# ebox.net
KiCad netlist of a schematic drawn in EAGLE
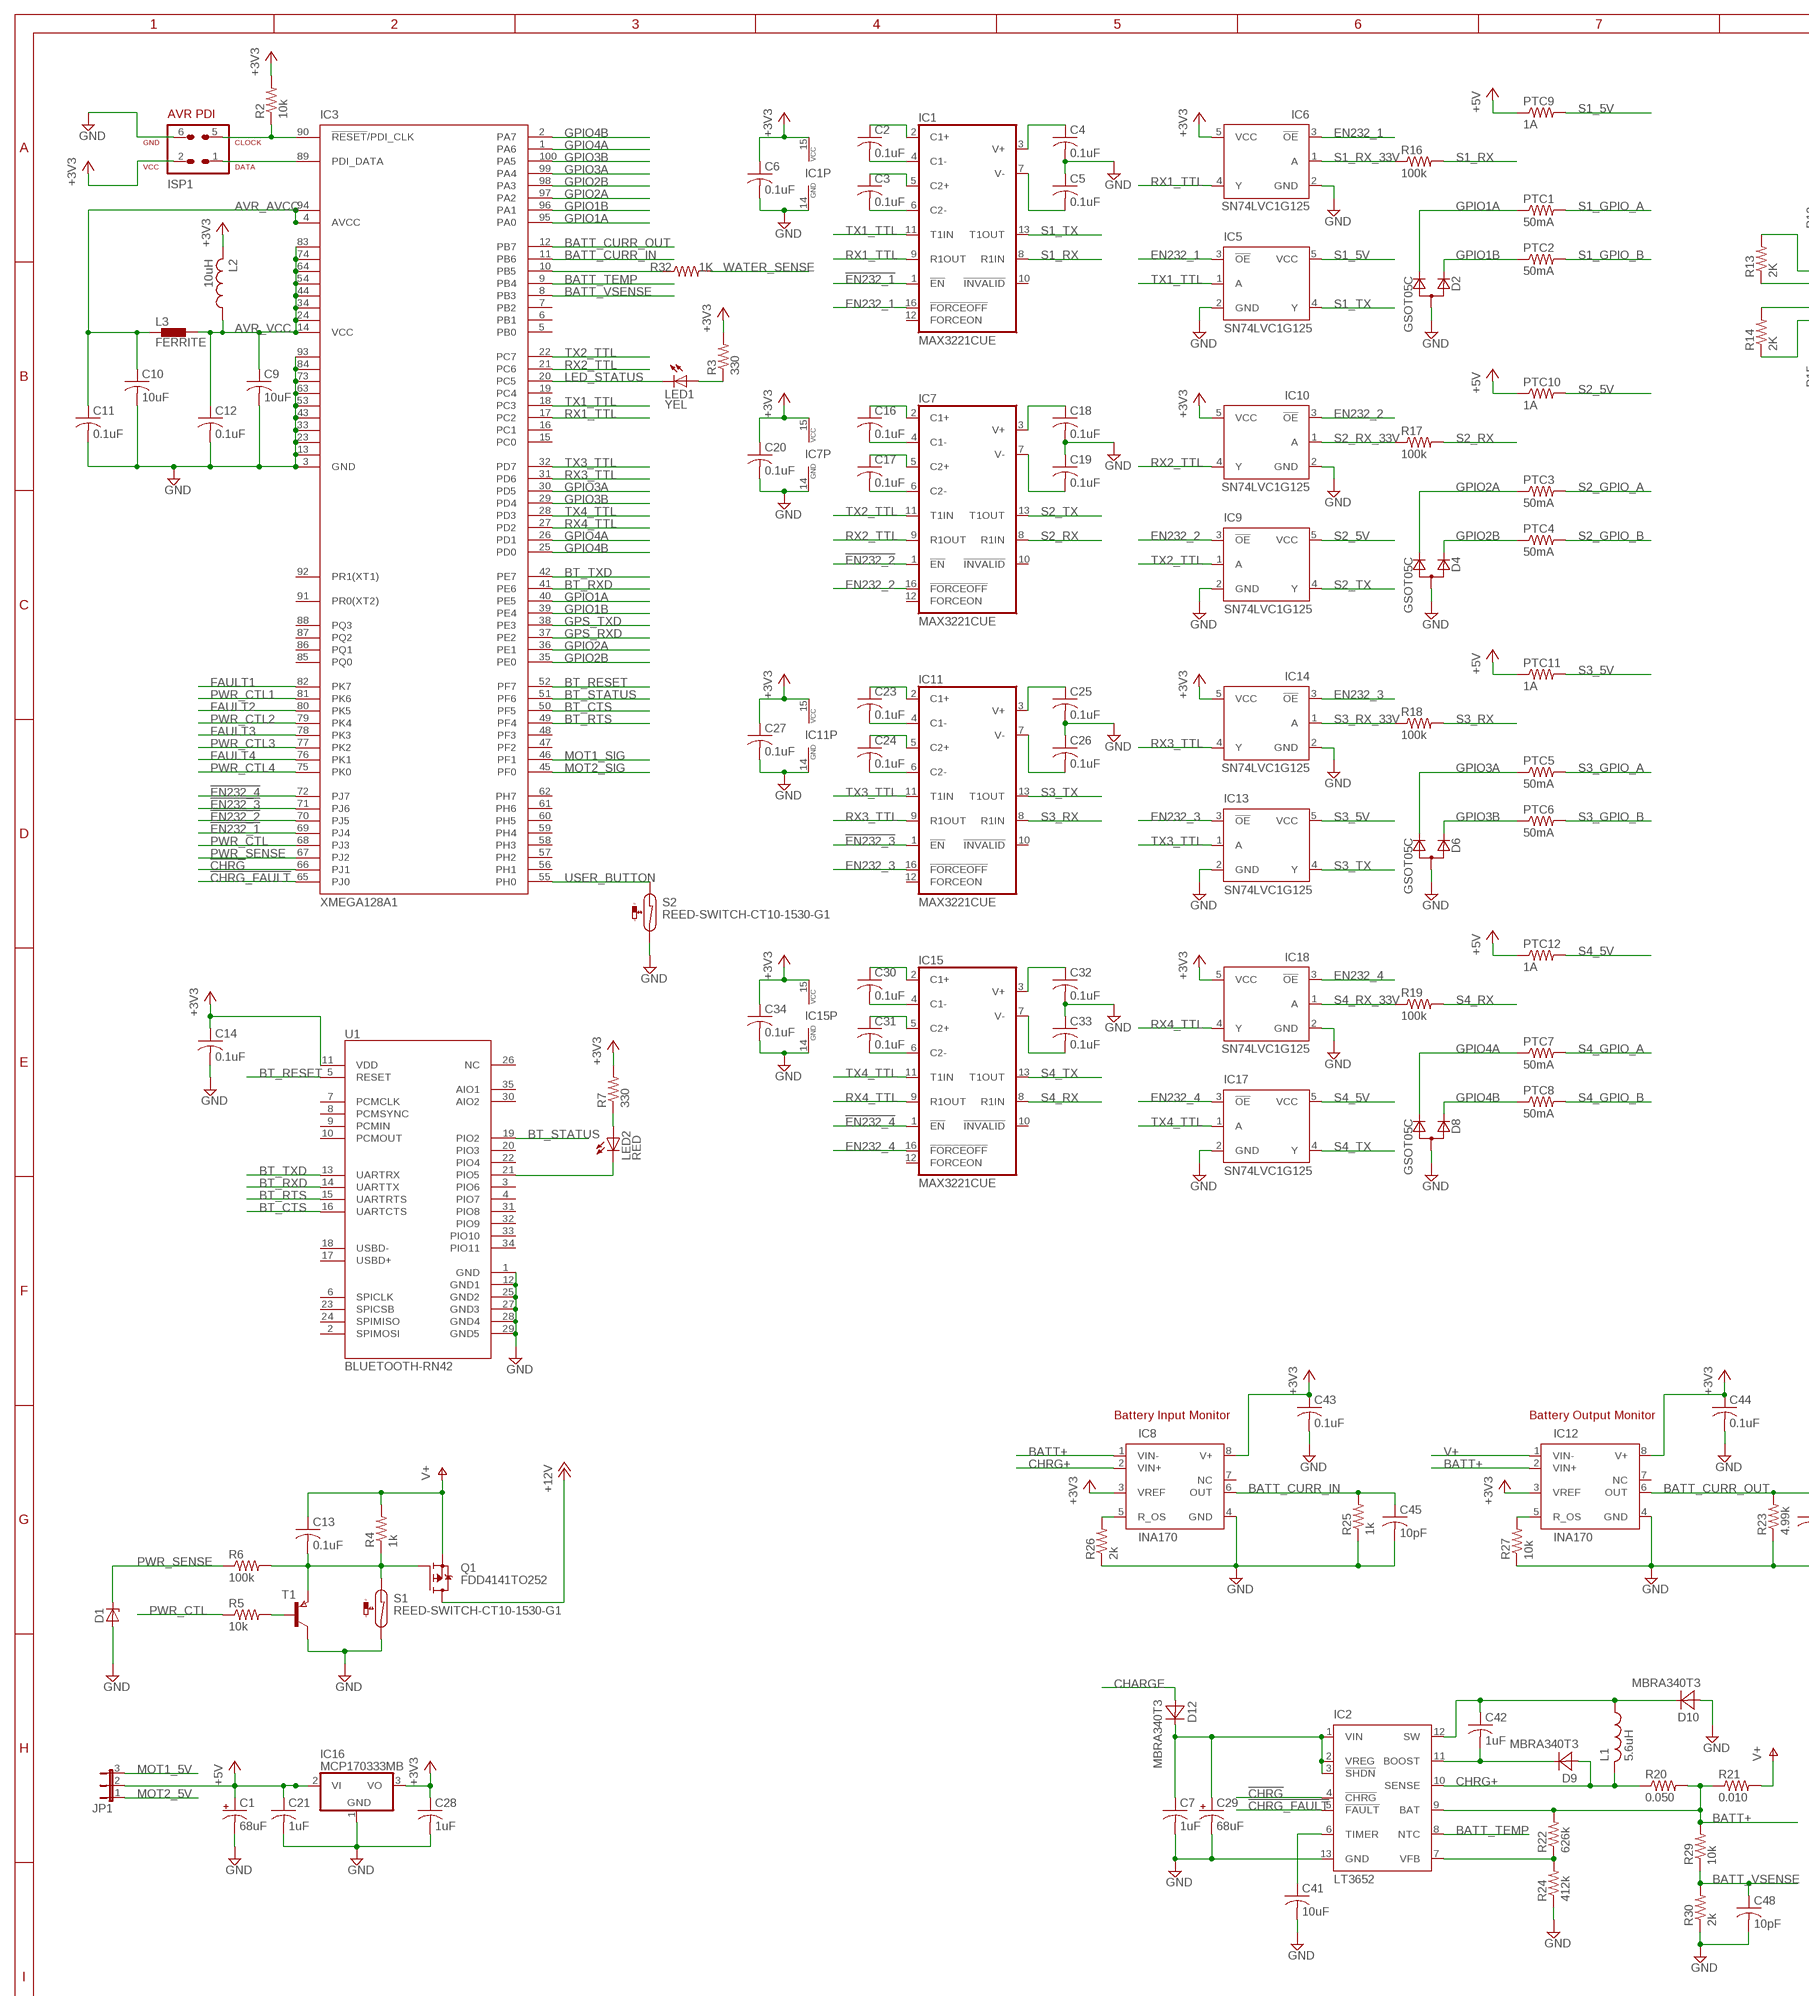
[diagram p0: schematic, sheet 1, part 1 of 2]
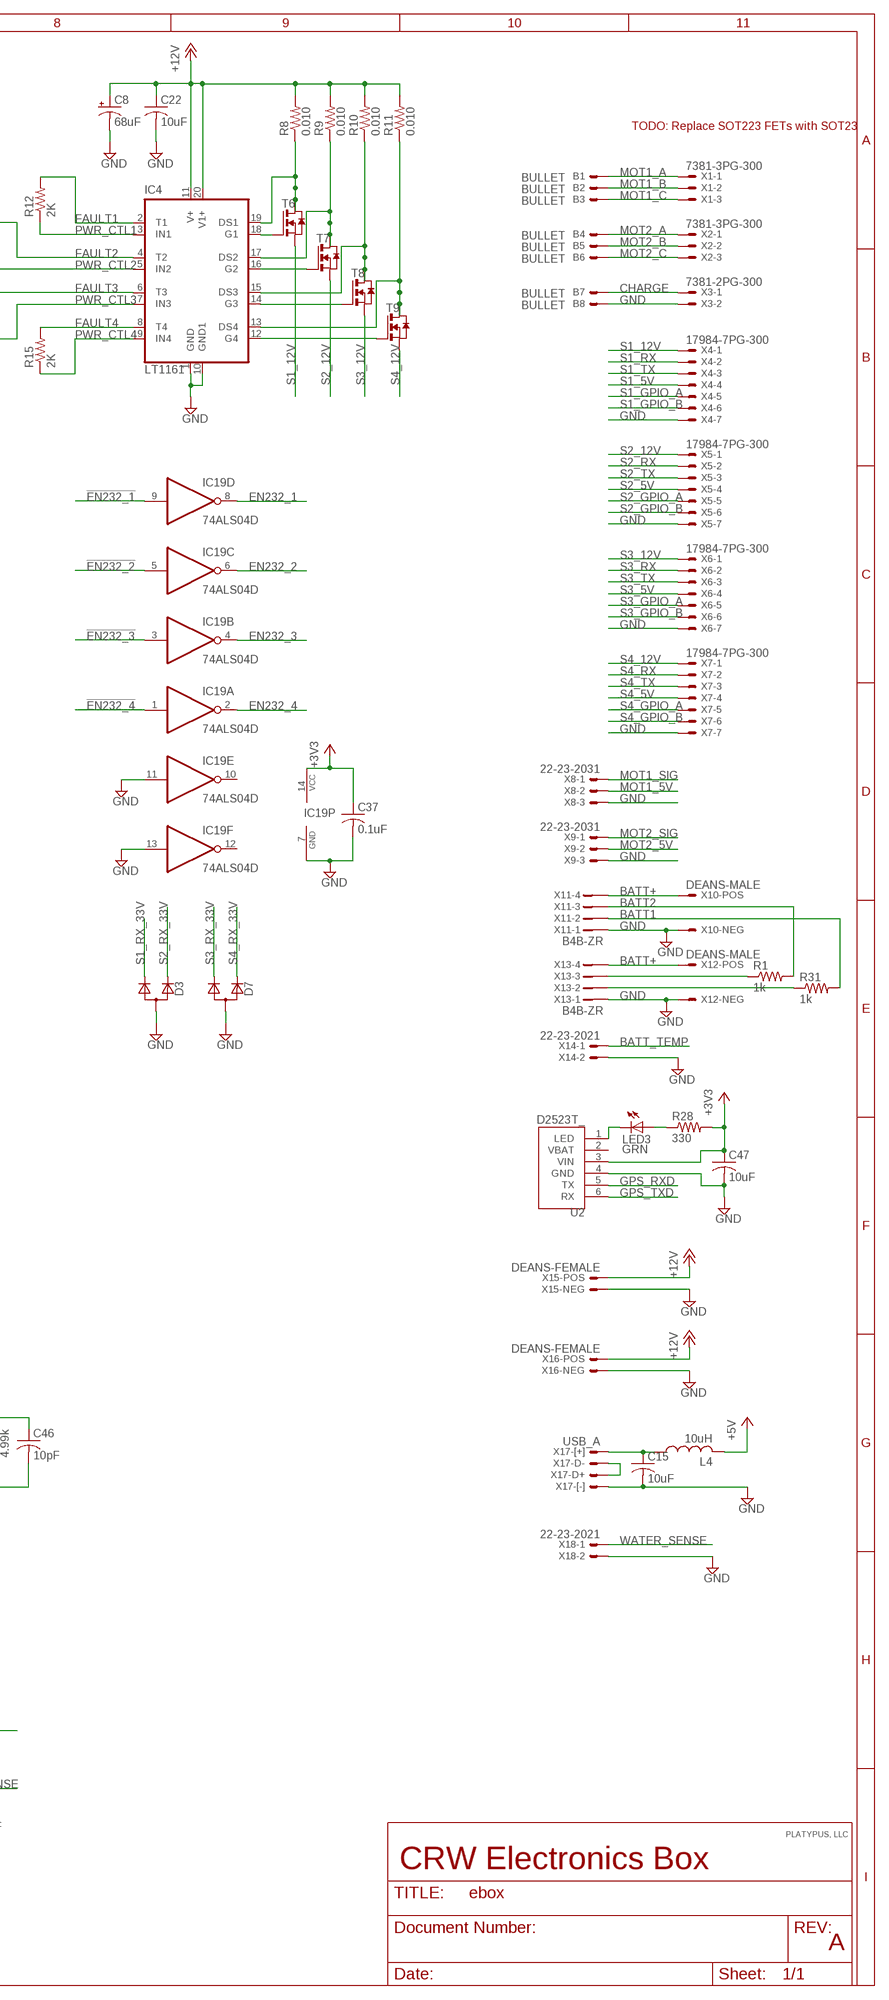
[diagram p1: schematic, sheet 1, part 2 of 2]

(export (version "E")
  (design (tool "Eeschema 10.0.6"))
  (components
    (comp (ref "B1")
      (value "BULLET")
      (footprint "eagle-import:BULLET")
      (libsource (lib "eagle-import") (part "BULLET"))
    )
    (comp (ref "B2")
      (value "BULLET")
      (footprint "eagle-import:BULLET")
      (libsource (lib "eagle-import") (part "BULLET"))
    )
    (comp (ref "B3")
      (value "BULLET")
      (footprint "eagle-import:BULLET")
      (libsource (lib "eagle-import") (part "BULLET"))
    )
    (comp (ref "B4")
      (value "BULLET")
      (footprint "eagle-import:BULLET")
      (libsource (lib "eagle-import") (part "BULLET"))
    )
    (comp (ref "B5")
      (value "BULLET")
      (footprint "eagle-import:BULLET")
      (libsource (lib "eagle-import") (part "BULLET"))
    )
    (comp (ref "B6")
      (value "BULLET")
      (footprint "eagle-import:BULLET")
      (libsource (lib "eagle-import") (part "BULLET"))
    )
    (comp (ref "B7")
      (value "BULLET")
      (footprint "eagle-import:BULLET")
      (libsource (lib "eagle-import") (part "BULLET"))
    )
    (comp (ref "B8")
      (value "BULLET")
      (footprint "eagle-import:BULLET")
      (libsource (lib "eagle-import") (part "BULLET"))
    )
    (comp (ref "C1")
      (value "68uF")
      (footprint "eagle-import:PANASONIC_D")
      (libsource (lib "eagle-import") (part "CPOL-USD"))
    )
    (comp (ref "C2")
      (value "0.1uF")
      (footprint "eagle-import:C0805")
      (libsource (lib "eagle-import") (part "C-USC0805"))
    )
    (comp (ref "C3")
      (value "0.1uF")
      (footprint "eagle-import:C0805")
      (libsource (lib "eagle-import") (part "C-USC0805"))
    )
    (comp (ref "C4")
      (value "0.1uF")
      (footprint "eagle-import:C0805")
      (libsource (lib "eagle-import") (part "C-USC0805"))
    )
    (comp (ref "C5")
      (value "0.1uF")
      (footprint "eagle-import:C0805")
      (libsource (lib "eagle-import") (part "C-USC0805"))
    )
    (comp (ref "C6")
      (value "0.1uF")
      (footprint "eagle-import:C0805")
      (libsource (lib "eagle-import") (part "C-USC0805"))
    )
    (comp (ref "C7")
      (value "1uF")
      (footprint "eagle-import:C0805")
      (libsource (lib "eagle-import") (part "C-USC0805"))
    )
    (comp (ref "C8")
      (value "68uF")
      (footprint "eagle-import:PANASONIC_D")
      (libsource (lib "eagle-import") (part "CPOL-USD"))
    )
    (comp (ref "C9")
      (value "10uF")
      (footprint "eagle-import:C0805")
      (libsource (lib "eagle-import") (part "C-USC0805"))
    )
    (comp (ref "C10")
      (value "10uF")
      (footprint "eagle-import:C0805")
      (libsource (lib "eagle-import") (part "C-USC0805"))
    )
    (comp (ref "C11")
      (value "0.1uF")
      (footprint "eagle-import:C0805")
      (libsource (lib "eagle-import") (part "C-USC0805"))
    )
    (comp (ref "C12")
      (value "0.1uF")
      (footprint "eagle-import:C0805")
      (libsource (lib "eagle-import") (part "C-USC0805"))
    )
    (comp (ref "C13")
      (value "0.1uF")
      (footprint "eagle-import:C0805")
      (libsource (lib "eagle-import") (part "C-USC0805"))
    )
    (comp (ref "C14")
      (value "0.1uF")
      (footprint "eagle-import:C0805")
      (libsource (lib "eagle-import") (part "C-USC0805"))
    )
    (comp (ref "C15")
      (value "10uF")
      (footprint "eagle-import:C0805")
      (libsource (lib "eagle-import") (part "C-USC0805"))
    )
    (comp (ref "C16")
      (value "0.1uF")
      (footprint "eagle-import:C0805")
      (libsource (lib "eagle-import") (part "C-USC0805"))
    )
    (comp (ref "C17")
      (value "0.1uF")
      (footprint "eagle-import:C0805")
      (libsource (lib "eagle-import") (part "C-USC0805"))
    )
    (comp (ref "C18")
      (value "0.1uF")
      (footprint "eagle-import:C0805")
      (libsource (lib "eagle-import") (part "C-USC0805"))
    )
    (comp (ref "C19")
      (value "0.1uF")
      (footprint "eagle-import:C0805")
      (libsource (lib "eagle-import") (part "C-USC0805"))
    )
    (comp (ref "C20")
      (value "0.1uF")
      (footprint "eagle-import:C0805")
      (libsource (lib "eagle-import") (part "C-USC0805"))
    )
    (comp (ref "C21")
      (value "1uF")
      (footprint "eagle-import:C0805")
      (libsource (lib "eagle-import") (part "C-USC0805"))
    )
    (comp (ref "C22")
      (value "10uF")
      (footprint "eagle-import:C0805")
      (libsource (lib "eagle-import") (part "C-USC0805"))
    )
    (comp (ref "C23")
      (value "0.1uF")
      (footprint "eagle-import:C0805")
      (libsource (lib "eagle-import") (part "C-USC0805"))
    )
    (comp (ref "C24")
      (value "0.1uF")
      (footprint "eagle-import:C0805")
      (libsource (lib "eagle-import") (part "C-USC0805"))
    )
    (comp (ref "C25")
      (value "0.1uF")
      (footprint "eagle-import:C0805")
      (libsource (lib "eagle-import") (part "C-USC0805"))
    )
    (comp (ref "C26")
      (value "0.1uF")
      (footprint "eagle-import:C0805")
      (libsource (lib "eagle-import") (part "C-USC0805"))
    )
    (comp (ref "C27")
      (value "0.1uF")
      (footprint "eagle-import:C0805")
      (libsource (lib "eagle-import") (part "C-USC0805"))
    )
    (comp (ref "C28")
      (value "1uF")
      (footprint "eagle-import:C0805")
      (libsource (lib "eagle-import") (part "C-USC0805"))
    )
    (comp (ref "C29")
      (value "68uF")
      (footprint "eagle-import:PANASONIC_D")
      (libsource (lib "eagle-import") (part "CPOL-USD"))
    )
    (comp (ref "C30")
      (value "0.1uF")
      (footprint "eagle-import:C0805")
      (libsource (lib "eagle-import") (part "C-USC0805"))
    )
    (comp (ref "C31")
      (value "0.1uF")
      (footprint "eagle-import:C0805")
      (libsource (lib "eagle-import") (part "C-USC0805"))
    )
    (comp (ref "C32")
      (value "0.1uF")
      (footprint "eagle-import:C0805")
      (libsource (lib "eagle-import") (part "C-USC0805"))
    )
    (comp (ref "C33")
      (value "0.1uF")
      (footprint "eagle-import:C0805")
      (libsource (lib "eagle-import") (part "C-USC0805"))
    )
    (comp (ref "C34")
      (value "0.1uF")
      (footprint "eagle-import:C0805")
      (libsource (lib "eagle-import") (part "C-USC0805"))
    )
    (comp (ref "C37")
      (value "0.1uF")
      (footprint "eagle-import:C0805")
      (libsource (lib "eagle-import") (part "C-USC0805"))
    )
    (comp (ref "C41")
      (value "10uF")
      (footprint "eagle-import:C0805")
      (libsource (lib "eagle-import") (part "C-USC0805"))
    )
    (comp (ref "C42")
      (value "1uF")
      (footprint "eagle-import:C0805")
      (libsource (lib "eagle-import") (part "C-USC0805"))
    )
    (comp (ref "C43")
      (value "0.1uF")
      (footprint "eagle-import:C0805")
      (libsource (lib "eagle-import") (part "C-USC0805"))
    )
    (comp (ref "C44")
      (value "0.1uF")
      (footprint "eagle-import:C0805")
      (libsource (lib "eagle-import") (part "C-USC0805"))
    )
    (comp (ref "C45")
      (value "10pF")
      (footprint "eagle-import:C0805")
      (libsource (lib "eagle-import") (part "C-USC0805"))
    )
    (comp (ref "C46")
      (value "10pF")
      (footprint "eagle-import:C0805")
      (libsource (lib "eagle-import") (part "C-USC0805"))
    )
    (comp (ref "C47")
      (value "10uF")
      (footprint "eagle-import:C0805")
      (libsource (lib "eagle-import") (part "C-USC0805"))
    )
    (comp (ref "C48")
      (value "10pF")
      (footprint "eagle-import:C0805")
      (libsource (lib "eagle-import") (part "C-USC0805"))
    )
    (comp (ref "D1")
      (value "ZENER-DIODESOT23")
      (footprint "eagle-import:SOT23")
      (libsource (lib "eagle-import") (part "ZENER-DIODESOT23"))
    )
    (comp (ref "D2")
      (value "GSOT05C")
      (footprint "eagle-import:SOT-23")
      (libsource (lib "eagle-import") (part "D_2CSOT23"))
    )
    (comp (ref "D3")
      (value "D_2CSOT23")
      (footprint "eagle-import:SOT-23")
      (libsource (lib "eagle-import") (part "D_2CSOT23"))
    )
    (comp (ref "D4")
      (value "GSOT05C")
      (footprint "eagle-import:SOT-23")
      (libsource (lib "eagle-import") (part "D_2CSOT23"))
    )
    (comp (ref "D6")
      (value "GSOT05C")
      (footprint "eagle-import:SOT-23")
      (libsource (lib "eagle-import") (part "D_2CSOT23"))
    )
    (comp (ref "D7")
      (value "D_2CSOT23")
      (footprint "eagle-import:SOT-23")
      (libsource (lib "eagle-import") (part "D_2CSOT23"))
    )
    (comp (ref "D8")
      (value "GSOT05C")
      (footprint "eagle-import:SOT-23")
      (libsource (lib "eagle-import") (part "D_2CSOT23"))
    )
    (comp (ref "D9")
      (value "MBRA340T3")
      (footprint "eagle-import:SMA")
      (libsource (lib "eagle-import") (part "MBRA340T3"))
    )
    (comp (ref "D10")
      (value "MBRA340T3")
      (footprint "eagle-import:SMA")
      (libsource (lib "eagle-import") (part "MBRA340T3"))
    )
    (comp (ref "D12")
      (value "MBRA340T3")
      (footprint "eagle-import:SMA")
      (libsource (lib "eagle-import") (part "MBRA340T3"))
    )
    (comp (ref "IC1")
      (value "MAX3221CUE")
      (footprint "eagle-import:TSSOP16")
      (fields (field (name "MF") "MAXIM") (field (name "MPN") "MAX3221CUE+"))
      (libsource (lib "eagle-import") (part "MAX3221UEC"))
    )
    (comp (ref "IC2")
      (value "LT3652")
      (footprint "eagle-import:MSOP12-MSE")
      (fields (field (name "MPN") "AD7992BRMZ-0"))
      (libsource (lib "eagle-import") (part "LT3652"))
    )
    (comp (ref "IC3")
      (value "XMEGA128A1")
      (footprint "eagle-import:TQFP100")
      (libsource (lib "eagle-import") (part "XMEGA128A1"))
    )
    (comp (ref "IC4")
      (value "LT1161")
      (footprint "eagle-import:SOIC20R")
      (libsource (lib "eagle-import") (part "LT1161"))
    )
    (comp (ref "IC5")
      (value "SN74LVC1G125")
      (footprint "eagle-import:SOT23-DBV")
      (libsource (lib "eagle-import") (part "SN74LVC1G125"))
    )
    (comp (ref "IC6")
      (value "SN74LVC1G125")
      (footprint "eagle-import:SOT23-DBV")
      (libsource (lib "eagle-import") (part "SN74LVC1G125"))
    )
    (comp (ref "IC7")
      (value "MAX3221CUE")
      (footprint "eagle-import:TSSOP16")
      (fields (field (name "MF") "MAXIM") (field (name "MPN") "MAX3221CUE+"))
      (libsource (lib "eagle-import") (part "MAX3221UEC"))
    )
    (comp (ref "IC8")
      (value "INA170")
      (footprint "eagle-import:MSOP8")
      (libsource (lib "eagle-import") (part "INA170"))
    )
    (comp (ref "IC9")
      (value "SN74LVC1G125")
      (footprint "eagle-import:SOT23-DBV")
      (libsource (lib "eagle-import") (part "SN74LVC1G125"))
    )
    (comp (ref "IC10")
      (value "SN74LVC1G125")
      (footprint "eagle-import:SOT23-DBV")
      (libsource (lib "eagle-import") (part "SN74LVC1G125"))
    )
    (comp (ref "IC11")
      (value "MAX3221CUE")
      (footprint "eagle-import:TSSOP16")
      (fields (field (name "MF") "MAXIM") (field (name "MPN") "MAX3221CUE+"))
      (libsource (lib "eagle-import") (part "MAX3221UEC"))
    )
    (comp (ref "IC12")
      (value "INA170")
      (footprint "eagle-import:MSOP8")
      (libsource (lib "eagle-import") (part "INA170"))
    )
    (comp (ref "IC13")
      (value "SN74LVC1G125")
      (footprint "eagle-import:SOT23-DBV")
      (libsource (lib "eagle-import") (part "SN74LVC1G125"))
    )
    (comp (ref "IC14")
      (value "SN74LVC1G125")
      (footprint "eagle-import:SOT23-DBV")
      (libsource (lib "eagle-import") (part "SN74LVC1G125"))
    )
    (comp (ref "IC15")
      (value "MAX3221CUE")
      (footprint "eagle-import:TSSOP16")
      (fields (field (name "MF") "MAXIM") (field (name "MPN") "MAX3221CUE+"))
      (libsource (lib "eagle-import") (part "MAX3221UEC"))
    )
    (comp (ref "IC16")
      (value "MCP170333MB")
      (footprint "eagle-import:SOT89")
      (libsource (lib "eagle-import") (part "MCP1703MB33"))
    )
    (comp (ref "IC17")
      (value "SN74LVC1G125")
      (footprint "eagle-import:SOT23-DBV")
      (libsource (lib "eagle-import") (part "SN74LVC1G125"))
    )
    (comp (ref "IC18")
      (value "SN74LVC1G125")
      (footprint "eagle-import:SOT23-DBV")
      (libsource (lib "eagle-import") (part "SN74LVC1G125"))
    )
    (comp (ref "IC19")
      (value "74ALS04D")
      (footprint "eagle-import:SO14")
      (libsource (lib "eagle-import") (part "7404DALS"))
    )
    (comp (ref "ISP1")
      (value "AVR-PDIVERT")
      (footprint "eagle-import:AVR-ISP-6")
      (libsource (lib "eagle-import") (part "AVR-PDIVERT"))
    )
    (comp (ref "JP1")
      (value "JP2E")
      (footprint "eagle-import:JP2")
      (libsource (lib "eagle-import") (part "JP2E"))
    )
    (comp (ref "L1")
      (value "5.6uH")
      (footprint "eagle-import:IHLP-2020CZ-11")
      (libsource (lib "eagle-import") (part "IHLP-2020CZ-11"))
    )
    (comp (ref "L2")
      (value "10uH")
      (footprint "eagle-import:L2012C")
      (libsource (lib "eagle-import") (part "L-USL2012C"))
    )
    (comp (ref "L3")
      (value "FERRITE")
      (footprint "eagle-import:0402")
      (libsource (lib "eagle-import") (part "BML15HB121SN1"))
    )
    (comp (ref "L4")
      (value "10uH")
      (footprint "eagle-import:L2012C")
      (libsource (lib "eagle-import") (part "L-USL2012C"))
    )
    (comp (ref "LED1")
      (value "YEL")
      (footprint "eagle-import:CHIPLED_1206")
      (libsource (lib "eagle-import") (part "LEDCHIPLED_1206"))
    )
    (comp (ref "LED2")
      (value "RED")
      (footprint "eagle-import:CHIPLED_1206")
      (libsource (lib "eagle-import") (part "LEDCHIPLED_1206"))
    )
    (comp (ref "LED3")
      (value "GRN")
      (footprint "eagle-import:CHIPLED_1206")
      (libsource (lib "eagle-import") (part "LEDCHIPLED_1206"))
    )
    (comp (ref "PTC1")
      (value "50mA")
      (footprint "eagle-import:R1206")
      (libsource (lib "eagle-import") (part "R-US_R1206"))
    )
    (comp (ref "PTC2")
      (value "50mA")
      (footprint "eagle-import:R1206")
      (libsource (lib "eagle-import") (part "R-US_R1206"))
    )
    (comp (ref "PTC3")
      (value "50mA")
      (footprint "eagle-import:R1206")
      (libsource (lib "eagle-import") (part "R-US_R1206"))
    )
    (comp (ref "PTC4")
      (value "50mA")
      (footprint "eagle-import:R1206")
      (libsource (lib "eagle-import") (part "R-US_R1206"))
    )
    (comp (ref "PTC5")
      (value "50mA")
      (footprint "eagle-import:R1206")
      (libsource (lib "eagle-import") (part "R-US_R1206"))
    )
    (comp (ref "PTC6")
      (value "50mA")
      (footprint "eagle-import:R1206")
      (libsource (lib "eagle-import") (part "R-US_R1206"))
    )
    (comp (ref "PTC7")
      (value "50mA")
      (footprint "eagle-import:R1206")
      (libsource (lib "eagle-import") (part "R-US_R1206"))
    )
    (comp (ref "PTC8")
      (value "50mA")
      (footprint "eagle-import:R1206")
      (libsource (lib "eagle-import") (part "R-US_R1206"))
    )
    (comp (ref "PTC9")
      (value "1A")
      (footprint "eagle-import:R1206")
      (libsource (lib "eagle-import") (part "R-US_R1206"))
    )
    (comp (ref "PTC10")
      (value "1A")
      (footprint "eagle-import:R1206")
      (libsource (lib "eagle-import") (part "R-US_R1206"))
    )
    (comp (ref "PTC11")
      (value "1A")
      (footprint "eagle-import:R1206")
      (libsource (lib "eagle-import") (part "R-US_R1206"))
    )
    (comp (ref "PTC12")
      (value "1A")
      (footprint "eagle-import:R1206")
      (libsource (lib "eagle-import") (part "R-US_R1206"))
    )
    (comp (ref "Q1")
      (value "FDD4141TO252")
      (footprint "eagle-import:TO252")
      (libsource (lib "eagle-import") (part "FDD4141TO252"))
    )
    (comp (ref "R1")
      (value "1k")
      (footprint "eagle-import:R0805")
      (libsource (lib "eagle-import") (part "R-US_R0805"))
    )
    (comp (ref "R2")
      (value "10k")
      (footprint "eagle-import:R0805")
      (libsource (lib "eagle-import") (part "R-US_R0805"))
    )
    (comp (ref "R3")
      (value "330")
      (footprint "eagle-import:R0805")
      (libsource (lib "eagle-import") (part "R-US_R0805"))
    )
    (comp (ref "R4")
      (value "1k")
      (footprint "eagle-import:R0805")
      (libsource (lib "eagle-import") (part "R-US_R0805"))
    )
    (comp (ref "R5")
      (value "10k")
      (footprint "eagle-import:R0805")
      (libsource (lib "eagle-import") (part "R-US_R0805"))
    )
    (comp (ref "R6")
      (value "100k")
      (footprint "eagle-import:R0805")
      (libsource (lib "eagle-import") (part "R-US_R0805"))
    )
    (comp (ref "R7")
      (value "330")
      (footprint "eagle-import:R0805")
      (libsource (lib "eagle-import") (part "R-US_R0805"))
    )
    (comp (ref "R8")
      (value "0.010")
      (footprint "eagle-import:R6332")
      (libsource (lib "eagle-import") (part "R-US_R6332"))
    )
    (comp (ref "R9")
      (value "0.010")
      (footprint "eagle-import:R6332")
      (libsource (lib "eagle-import") (part "R-US_R6332"))
    )
    (comp (ref "R10")
      (value "0.010")
      (footprint "eagle-import:R6332")
      (libsource (lib "eagle-import") (part "R-US_R6332"))
    )
    (comp (ref "R11")
      (value "0.010")
      (footprint "eagle-import:R6332")
      (libsource (lib "eagle-import") (part "R-US_R6332"))
    )
    (comp (ref "R12")
      (value "2K")
      (footprint "eagle-import:R0805")
      (libsource (lib "eagle-import") (part "R-US_R0805"))
    )
    (comp (ref "R13")
      (value "2K")
      (footprint "eagle-import:R0805")
      (libsource (lib "eagle-import") (part "R-US_R0805"))
    )
    (comp (ref "R14")
      (value "2K")
      (footprint "eagle-import:R0805")
      (libsource (lib "eagle-import") (part "R-US_R0805"))
    )
    (comp (ref "R15")
      (value "2K")
      (footprint "eagle-import:R0805")
      (libsource (lib "eagle-import") (part "R-US_R0805"))
    )
    (comp (ref "R16")
      (value "100k")
      (footprint "eagle-import:R0805")
      (libsource (lib "eagle-import") (part "R-US_R0805"))
    )
    (comp (ref "R17")
      (value "100k")
      (footprint "eagle-import:R0805")
      (libsource (lib "eagle-import") (part "R-US_R0805"))
    )
    (comp (ref "R18")
      (value "100k")
      (footprint "eagle-import:R0805")
      (libsource (lib "eagle-import") (part "R-US_R0805"))
    )
    (comp (ref "R19")
      (value "100k")
      (footprint "eagle-import:R0805")
      (libsource (lib "eagle-import") (part "R-US_R0805"))
    )
    (comp (ref "R20")
      (value "0.050")
      (footprint "eagle-import:R6332")
      (libsource (lib "eagle-import") (part "R-US_R6332"))
    )
    (comp (ref "R21")
      (value "0.010")
      (footprint "eagle-import:R6332")
      (libsource (lib "eagle-import") (part "R-US_R6332"))
    )
    (comp (ref "R22")
      (value "626k")
      (footprint "eagle-import:R0805")
      (libsource (lib "eagle-import") (part "R-US_R0805"))
    )
    (comp (ref "R23")
      (value "4.99k")
      (footprint "eagle-import:R0805")
      (libsource (lib "eagle-import") (part "R-US_R0805"))
    )
    (comp (ref "R24")
      (value "412k")
      (footprint "eagle-import:R0805")
      (libsource (lib "eagle-import") (part "R-US_R0805"))
    )
    (comp (ref "R25")
      (value "1k")
      (footprint "eagle-import:R0805")
      (libsource (lib "eagle-import") (part "R-US_R0805"))
    )
    (comp (ref "R26")
      (value "2k")
      (footprint "eagle-import:R0805")
      (libsource (lib "eagle-import") (part "R-US_R0805"))
    )
    (comp (ref "R27")
      (value "10k")
      (footprint "eagle-import:R0805")
      (libsource (lib "eagle-import") (part "R-US_R0805"))
    )
    (comp (ref "R28")
      (value "330")
      (footprint "eagle-import:R0805")
      (libsource (lib "eagle-import") (part "R-US_R0805"))
    )
    (comp (ref "R29")
      (value "10k")
      (footprint "eagle-import:R0805")
      (libsource (lib "eagle-import") (part "R-US_R0805"))
    )
    (comp (ref "R30")
      (value "2k")
      (footprint "eagle-import:R0805")
      (libsource (lib "eagle-import") (part "R-US_R0805"))
    )
    (comp (ref "R31")
      (value "1k")
      (footprint "eagle-import:R0805")
      (libsource (lib "eagle-import") (part "R-US_R0805"))
    )
    (comp (ref "R32")
      (value "1K")
      (footprint "eagle-import:R0805")
      (libsource (lib "eagle-import") (part "R-US_R0805"))
    )
    (comp (ref "S1")
      (value "REED-SWITCH-CT10-1530-G1")
      (footprint "eagle-import:CT10-G1")
      (fields (field (name "MF") "COTO TECHNOLOGY") (field (name "MPN") "CT10-1530-G1"))
      (libsource (lib "eagle-import") (part "REED-SWITCH-CT10-1530-G1"))
    )
    (comp (ref "S2")
      (value "REED-SWITCH-CT10-1530-G1")
      (footprint "eagle-import:CT10-G1")
      (fields (field (name "MF") "COTO TECHNOLOGY") (field (name "MPN") "CT10-1530-G1"))
      (libsource (lib "eagle-import") (part "REED-SWITCH-CT10-1530-G1"))
    )
    (comp (ref "T1")
      (value "PNPSOT23")
      (footprint "eagle-import:SOT-23")
      (fields (field (name "MPN") "DSS20200L-7"))
      (libsource (lib "eagle-import") (part "PNPSOT23"))
    )
    (comp (ref "T6")
      (value "NMOSSOT23-6")
      (footprint "eagle-import:SOT23-6")
      (libsource (lib "eagle-import") (part "NMOSSOT23-6"))
    )
    (comp (ref "T7")
      (value "NMOSSOT23-6")
      (footprint "eagle-import:SOT23-6")
      (libsource (lib "eagle-import") (part "NMOSSOT23-6"))
    )
    (comp (ref "T8")
      (value "NMOSSOT23-6")
      (footprint "eagle-import:SOT23-6")
      (libsource (lib "eagle-import") (part "NMOSSOT23-6"))
    )
    (comp (ref "T9")
      (value "NMOSSOT23-6")
      (footprint "eagle-import:SOT23-6")
      (libsource (lib "eagle-import") (part "NMOSSOT23-6"))
    )
    (comp (ref "U$1")
      (value "PLATYPUS_LOGO")
      (footprint "eagle-import:PLATYPUS_LOGO_SMALL")
      (libsource (lib "eagle-import") (part "PLATYPUS_LOGO"))
    )
    (comp (ref "U1")
      (value "BLUETOOTH-RN42")
      (footprint "eagle-import:RN41")
      (libsource (lib "eagle-import") (part "BLUETOOTH-RN41{dblquote}"))
    )
    (comp (ref "U2")
      (value "D2523T_")
      (footprint "eagle-import:EM406")
      (libsource (lib "eagle-import") (part "D2523T_"))
    )
    (comp (ref "X1")
      (value "7381-3PG-300")
      (footprint "eagle-import:7381-3PG-300")
      (libsource (lib "eagle-import") (part "7381-3PG-300"))
    )
    (comp (ref "X2")
      (value "7381-3PG-300")
      (footprint "eagle-import:7381-3PG-300")
      (libsource (lib "eagle-import") (part "7381-3PG-300"))
    )
    (comp (ref "X3")
      (value "7381-2PG-300")
      (footprint "eagle-import:7381-2PG-300")
      (libsource (lib "eagle-import") (part "7381-2PG-300"))
    )
    (comp (ref "X4")
      (value "17984-7PG-300")
      (footprint "eagle-import:17984-7PG-300")
      (libsource (lib "eagle-import") (part "17984-7PG-300"))
    )
    (comp (ref "X5")
      (value "17984-7PG-300")
      (footprint "eagle-import:17984-7PG-300")
      (libsource (lib "eagle-import") (part "17984-7PG-300"))
    )
    (comp (ref "X6")
      (value "17984-7PG-300")
      (footprint "eagle-import:17984-7PG-300")
      (libsource (lib "eagle-import") (part "17984-7PG-300"))
    )
    (comp (ref "X7")
      (value "17984-7PG-300")
      (footprint "eagle-import:17984-7PG-300")
      (libsource (lib "eagle-import") (part "17984-7PG-300"))
    )
    (comp (ref "X8")
      (value "22-23-2031")
      (footprint "eagle-import:22-23-2031")
      (fields (field (name "MF") "MOLEX"))
      (libsource (lib "eagle-import") (part "22-23-2031"))
    )
    (comp (ref "X9")
      (value "22-23-2031")
      (footprint "eagle-import:22-23-2031")
      (fields (field (name "MF") "MOLEX"))
      (libsource (lib "eagle-import") (part "22-23-2031"))
    )
    (comp (ref "X10")
      (value "DEANS-MALE")
      (footprint "eagle-import:DEANS_MALE")
      (libsource (lib "eagle-import") (part "DEANS-MALE"))
    )
    (comp (ref "X11")
      (value "B4B-ZR")
      (footprint "eagle-import:B4B-ZR")
      (fields (field (name "MF") "FARNELL") (field (name "MPN") "B4B-ZR(LF)(SN)"))
      (libsource (lib "eagle-import") (part "?4B-ZRB"))
    )
    (comp (ref "X12")
      (value "DEANS-MALE")
      (footprint "eagle-import:DEANS_MALE")
      (libsource (lib "eagle-import") (part "DEANS-MALE"))
    )
    (comp (ref "X13")
      (value "B4B-ZR")
      (footprint "eagle-import:B4B-ZR")
      (fields (field (name "MF") "FARNELL") (field (name "MPN") "B4B-ZR(LF)(SN)"))
      (libsource (lib "eagle-import") (part "?4B-ZRB"))
    )
    (comp (ref "X14")
      (value "22-23-2021")
      (footprint "eagle-import:22-23-2021")
      (fields (field (name "MF") "MOLEX"))
      (libsource (lib "eagle-import") (part "22-23-2021"))
    )
    (comp (ref "X15")
      (value "DEANS-FEMALE")
      (footprint "eagle-import:DEANS_FEMALE")
      (libsource (lib "eagle-import") (part "DEANS-FEMALE"))
    )
    (comp (ref "X16")
      (value "DEANS-FEMALE")
      (footprint "eagle-import:DEANS_FEMALE")
      (libsource (lib "eagle-import") (part "DEANS-FEMALE"))
    )
    (comp (ref "X17")
      (value "USB_A")
      (footprint "eagle-import:1001-002-01100")
      (libsource (lib "eagle-import") (part "USB_A"))
    )
    (comp (ref "X18")
      (value "22-23-2021")
      (footprint "eagle-import:22-23-2021")
      (fields
        (field (name "MF") "MOLEX")
        (field (name "MF_1") "MOLEX")
        (field (name "MPN") "22-23-2021")
        (field (name "OC_FARNELL") "1462926")
        (field (name "OC_NEWARK") "25C3832")
      )
      (libsource (lib "eagle-import") (part "22-23-2021"))
    )
  )
  (nets
    (net (code "1") (name "+3V3") (class "Default")
      (node (ref "C14") (pin "1") (pinfunction "1_1") (pintype "passive"))
      (node (ref "C20") (pin "1") (pinfunction "1_1") (pintype "passive"))
      (node (ref "C27") (pin "1") (pinfunction "1_1") (pintype "passive"))
      (node (ref "C28") (pin "1") (pinfunction "1_1") (pintype "passive"))
      (node (ref "C34") (pin "1") (pinfunction "1_1") (pintype "passive"))
      (node (ref "C37") (pin "1") (pinfunction "1_1") (pintype "passive"))
      (node (ref "C43") (pin "1") (pinfunction "1_1") (pintype "passive"))
      (node (ref "C44") (pin "1") (pinfunction "1_1") (pintype "passive"))
      (node (ref "C47") (pin "1") (pinfunction "1_1") (pintype "passive"))
      (node (ref "C6") (pin "1") (pinfunction "1_1") (pintype "passive"))
      (node (ref "IC1") (pin "15") (pinfunction "VCC_15") (pintype "power_in"))
      (node (ref "IC10") (pin "5") (pinfunction "VCC_5") (pintype "passive"))
      (node (ref "IC11") (pin "15") (pinfunction "VCC_15") (pintype "power_in"))
      (node (ref "IC12") (pin "3") (pinfunction "VREF_3") (pintype "input"))
      (node (ref "IC12") (pin "8") (pinfunction "V+_8") (pintype "input"))
      (node (ref "IC14") (pin "5") (pinfunction "VCC_5") (pintype "passive"))
      (node (ref "IC15") (pin "15") (pinfunction "VCC_15") (pintype "power_in"))
      (node (ref "IC16") (pin "3") (pinfunction "VO_3") (pintype "passive"))
      (node (ref "IC18") (pin "5") (pinfunction "VCC_5") (pintype "passive"))
      (node (ref "IC19") (pin "14") (pinfunction "VCC_14") (pintype "power_in"))
      (node (ref "IC6") (pin "5") (pinfunction "VCC_5") (pintype "passive"))
      (node (ref "IC7") (pin "15") (pinfunction "VCC_15") (pintype "power_in"))
      (node (ref "IC8") (pin "3") (pinfunction "VREF_3") (pintype "input"))
      (node (ref "IC8") (pin "8") (pinfunction "V+_8") (pintype "input"))
      (node (ref "ISP1") (pin "2") (pinfunction "2_2") (pintype "passive"))
      (node (ref "L2") (pin "2") (pinfunction "2_2") (pintype "passive"))
      (node (ref "R2") (pin "2") (pinfunction "2_2") (pintype "passive"))
      (node (ref "R28") (pin "2") (pinfunction "2_2") (pintype "passive"))
      (node (ref "R3") (pin "2") (pinfunction "2_2") (pintype "passive"))
      (node (ref "R7") (pin "2") (pinfunction "2_2") (pintype "passive"))
      (node (ref "U1") (pin "11") (pinfunction "VDD_11") (pintype "bidirectional"))
      (node (ref "U2") (pin "3") (pinfunction "VIN_3") (pintype "bidirectional"))
    )
    (net (code "2") (name "+5V") (class "Default")
      (node (ref "C1") (pin "+") (pinfunction "+_+") (pintype "passive"))
      (node (ref "C21") (pin "1") (pinfunction "1_1") (pintype "passive"))
      (node (ref "IC16") (pin "2") (pinfunction "VI_2") (pintype "input"))
      (node (ref "IC16") (pin "2@1") (pinfunction "VI1_2@1") (pintype "input"))
      (node (ref "JP1") (pin "2") (pinfunction "2_2") (pintype "passive"))
      (node (ref "L4") (pin "2") (pinfunction "2_2") (pintype "passive"))
      (node (ref "PTC10") (pin "1") (pinfunction "1_1") (pintype "passive"))
      (node (ref "PTC11") (pin "1") (pinfunction "1_1") (pintype "passive"))
      (node (ref "PTC12") (pin "1") (pinfunction "1_1") (pintype "passive"))
      (node (ref "PTC9") (pin "1") (pinfunction "1_1") (pintype "passive"))
    )
    (net (code "3") (name "+12V") (class "Default")
      (node (ref "C22") (pin "1") (pinfunction "1_1") (pintype "passive"))
      (node (ref "C8") (pin "+") (pinfunction "+_+") (pintype "passive"))
      (node (ref "IC4") (pin "11") (pinfunction "V+_11") (pintype "input"))
      (node (ref "IC4") (pin "20") (pinfunction "V1+_20") (pintype "input"))
      (node (ref "Q1") (pin "3") (pinfunction "D_3") (pintype "passive"))
      (node (ref "R10") (pin "2") (pinfunction "2_2") (pintype "passive"))
      (node (ref "R11") (pin "2") (pinfunction "2_2") (pintype "passive"))
      (node (ref "R8") (pin "2") (pinfunction "2_2") (pintype "passive"))
      (node (ref "R9") (pin "2") (pinfunction "2_2") (pintype "passive"))
      (node (ref "X15") (pin "POS") (pinfunction "S_POS") (pintype "passive"))
      (node (ref "X16") (pin "POS") (pinfunction "S_POS") (pintype "passive"))
    )
    (net (code "4") (name "/AVR_AVCC") (class "Default")
      (node (ref "C10") (pin "1") (pinfunction "1_1") (pintype "passive"))
      (node (ref "C11") (pin "1") (pinfunction "1_1") (pintype "passive"))
      (node (ref "IC3") (pin "4") (pinfunction "AVCC_4") (pintype "power_in"))
      (node (ref "IC3") (pin "94") (pinfunction "AVCC1_94") (pintype "power_in"))
      (node (ref "L3") (pin "1") (pinfunction "1_1") (pintype "passive"))
    )
    (net (code "5") (name "/AVR_VCC") (class "Default")
      (node (ref "C12") (pin "1") (pinfunction "1_1") (pintype "passive"))
      (node (ref "C9") (pin "1") (pinfunction "1_1") (pintype "passive"))
      (node (ref "IC3") (pin "14") (pinfunction "VCC_14") (pintype "power_in"))
      (node (ref "IC3") (pin "24") (pinfunction "VCC1_24") (pintype "power_in"))
      (node (ref "IC3") (pin "34") (pinfunction "VCC2_34") (pintype "power_in"))
      (node (ref "IC3") (pin "44") (pinfunction "VCC3_44") (pintype "power_in"))
      (node (ref "IC3") (pin "54") (pinfunction "VCC4_54") (pintype "power_in"))
      (node (ref "IC3") (pin "64") (pinfunction "VCC5_64") (pintype "power_in"))
      (node (ref "IC3") (pin "74") (pinfunction "VCC6_74") (pintype "power_in"))
      (node (ref "IC3") (pin "83") (pinfunction "VCC7_83") (pintype "power_in"))
      (node (ref "L2") (pin "1") (pinfunction "1_1") (pintype "passive"))
      (node (ref "L3") (pin "2") (pinfunction "2_2") (pintype "passive"))
    )
    (net (code "6") (name "/BATT+") (class "Default")
      (node (ref "IC12") (pin "2") (pinfunction "VIN+_2") (pintype "passive"))
      (node (ref "IC2") (pin "9") (pinfunction "BAT_9") (pintype "input"))
      (node (ref "IC8") (pin "1") (pinfunction "VIN-_1") (pintype "passive"))
      (node (ref "R20") (pin "2") (pinfunction "2_2") (pintype "passive"))
      (node (ref "R21") (pin "1") (pinfunction "1_1") (pintype "passive"))
      (node (ref "R22") (pin "2") (pinfunction "2_2") (pintype "passive"))
      (node (ref "R29") (pin "2") (pinfunction "2_2") (pintype "passive"))
      (node (ref "X10") (pin "POS") (pinfunction "S_POS") (pintype "passive"))
      (node (ref "X11") (pin "4") (pinfunction "1_4") (pintype "passive"))
      (node (ref "X12") (pin "POS") (pinfunction "S_POS") (pintype "passive"))
      (node (ref "X13") (pin "4") (pinfunction "1_4") (pintype "passive"))
    )
    (net (code "7") (name "/BATT1") (class "Default")
      (node (ref "R31") (pin "2") (pinfunction "2_2") (pintype "passive"))
      (node (ref "X11") (pin "2") (pinfunction "1_2") (pintype "passive"))
    )
    (net (code "8") (name "/BATT2") (class "Default")
      (node (ref "R1") (pin "2") (pinfunction "2_2") (pintype "passive"))
      (node (ref "X11") (pin "3") (pinfunction "1_3") (pintype "passive"))
    )
    (net (code "9") (name "/BATT_CURR_IN") (class "Default")
      (node (ref "C45") (pin "1") (pinfunction "1_1") (pintype "passive"))
      (node (ref "IC3") (pin "11") (pinfunction "PB6_11") (pintype "bidirectional"))
      (node (ref "IC8") (pin "6") (pinfunction "OUT_6") (pintype "passive"))
      (node (ref "R25") (pin "2") (pinfunction "2_2") (pintype "passive"))
    )
    (net (code "10") (name "/BATT_CURR_OUT") (class "Default")
      (node (ref "C46") (pin "1") (pinfunction "1_1") (pintype "passive"))
      (node (ref "IC12") (pin "6") (pinfunction "OUT_6") (pintype "passive"))
      (node (ref "IC3") (pin "12") (pinfunction "PB7_12") (pintype "bidirectional"))
      (node (ref "R23") (pin "2") (pinfunction "2_2") (pintype "passive"))
    )
    (net (code "11") (name "/BATT_TEMP") (class "Default")
      (node (ref "IC2") (pin "8") (pinfunction "NTC_8") (pintype "bidirectional"))
      (node (ref "IC3") (pin "9") (pinfunction "PB4_9") (pintype "bidirectional"))
      (node (ref "X14") (pin "1") (pinfunction "S_1") (pintype "passive"))
    )
    (net (code "12") (name "/BATT_VSENSE") (class "Default")
      (node (ref "C48") (pin "1") (pinfunction "1_1") (pintype "passive"))
      (node (ref "IC3") (pin "8") (pinfunction "PB3_8") (pintype "bidirectional"))
      (node (ref "R29") (pin "1") (pinfunction "1_1") (pintype "passive"))
      (node (ref "R30") (pin "2") (pinfunction "2_2") (pintype "passive"))
    )
    (net (code "13") (name "/BT_CTS") (class "Default")
      (node (ref "IC3") (pin "50") (pinfunction "PF5_50") (pintype "bidirectional"))
      (node (ref "U1") (pin "16") (pinfunction "UARTCTS_16") (pintype "bidirectional"))
    )
    (net (code "14") (name "/BT_RESET") (class "Default")
      (node (ref "IC3") (pin "52") (pinfunction "PF7_52") (pintype "bidirectional"))
      (node (ref "U1") (pin "5") (pinfunction "RESET_5") (pintype "bidirectional"))
    )
    (net (code "15") (name "/BT_RTS") (class "Default")
      (node (ref "IC3") (pin "49") (pinfunction "PF4_49") (pintype "bidirectional"))
      (node (ref "U1") (pin "15") (pinfunction "UARTRTS_15") (pintype "bidirectional"))
    )
    (net (code "16") (name "/BT_RXD") (class "Default")
      (node (ref "IC3") (pin "41") (pinfunction "PE6_41") (pintype "bidirectional"))
      (node (ref "U1") (pin "14") (pinfunction "UARTTX_14") (pintype "bidirectional"))
    )
    (net (code "17") (name "/BT_STATUS") (class "Default")
      (node (ref "IC3") (pin "51") (pinfunction "PF6_51") (pintype "bidirectional"))
      (node (ref "U1") (pin "19") (pinfunction "PIO2_19") (pintype "bidirectional"))
    )
    (net (code "18") (name "/BT_TXD") (class "Default")
      (node (ref "IC3") (pin "42") (pinfunction "PE7_42") (pintype "bidirectional"))
      (node (ref "U1") (pin "13") (pinfunction "UARTRX_13") (pintype "bidirectional"))
    )
    (net (code "19") (name "/CHARGE") (class "Default")
      (node (ref "B7") (pin "P$1") (pinfunction "S_P$1") (pintype "passive"))
      (node (ref "D12") (pin "A") (pinfunction "A_A") (pintype "passive"))
      (node (ref "X3") (pin "1") (pinfunction "S_1") (pintype "passive"))
    )
    (net (code "20") (name "/CHRG+") (class "Default")
      (node (ref "D9") (pin "A") (pinfunction "A_A") (pintype "passive"))
      (node (ref "IC2") (pin "10") (pinfunction "SENSE_10") (pintype "input"))
      (node (ref "IC8") (pin "2") (pinfunction "VIN+_2") (pintype "passive"))
      (node (ref "L1") (pin "2") (pinfunction "2_2") (pintype "passive"))
      (node (ref "R20") (pin "1") (pinfunction "1_1") (pintype "passive"))
    )
    (net (code "21") (name "/EN232_1") (class "Default")
      (node (ref "IC1") (pin "16") (pinfunction "~{FORCEOFF}_16") (pintype "input"))
      (node (ref "IC19") (pin "8") (pinfunction "O_8") (pintype "output"))
      (node (ref "IC5") (pin "3") (pinfunction "~{OE}_3") (pintype "input"))
      (node (ref "IC6") (pin "3") (pinfunction "~{OE}_3") (pintype "input"))
    )
    (net (code "22") (name "/EN232_2") (class "Default")
      (node (ref "IC10") (pin "3") (pinfunction "~{OE}_3") (pintype "input"))
      (node (ref "IC19") (pin "6") (pinfunction "O_6") (pintype "output"))
      (node (ref "IC7") (pin "16") (pinfunction "~{FORCEOFF}_16") (pintype "input"))
      (node (ref "IC9") (pin "3") (pinfunction "~{OE}_3") (pintype "input"))
    )
    (net (code "23") (name "/EN232_3") (class "Default")
      (node (ref "IC11") (pin "16") (pinfunction "~{FORCEOFF}_16") (pintype "input"))
      (node (ref "IC13") (pin "3") (pinfunction "~{OE}_3") (pintype "input"))
      (node (ref "IC14") (pin "3") (pinfunction "~{OE}_3") (pintype "input"))
      (node (ref "IC19") (pin "4") (pinfunction "O_4") (pintype "output"))
    )
    (net (code "24") (name "/EN232_4") (class "Default")
      (node (ref "IC15") (pin "16") (pinfunction "~{FORCEOFF}_16") (pintype "input"))
      (node (ref "IC17") (pin "3") (pinfunction "~{OE}_3") (pintype "input"))
      (node (ref "IC18") (pin "3") (pinfunction "~{OE}_3") (pintype "input"))
      (node (ref "IC19") (pin "2") (pinfunction "O_2") (pintype "output"))
    )
    (net (code "25") (name "/FAULT1") (class "Default")
      (node (ref "IC3") (pin "82") (pinfunction "PK7_82") (pintype "bidirectional"))
      (node (ref "IC4") (pin "2") (pinfunction "T1_2") (pintype "bidirectional"))
      (node (ref "R12") (pin "2") (pinfunction "2_2") (pintype "passive"))
    )
    (net (code "26") (name "/FAULT2") (class "Default")
      (node (ref "IC3") (pin "80") (pinfunction "PK5_80") (pintype "bidirectional"))
      (node (ref "IC4") (pin "4") (pinfunction "T2_4") (pintype "bidirectional"))
      (node (ref "R13") (pin "2") (pinfunction "2_2") (pintype "passive"))
    )
    (net (code "27") (name "/FAULT3") (class "Default")
      (node (ref "IC3") (pin "78") (pinfunction "PK3_78") (pintype "bidirectional"))
      (node (ref "IC4") (pin "6") (pinfunction "T3_6") (pintype "bidirectional"))
      (node (ref "R14") (pin "2") (pinfunction "2_2") (pintype "passive"))
    )
    (net (code "28") (name "/FAULT4") (class "Default")
      (node (ref "IC3") (pin "76") (pinfunction "PK1_76") (pintype "bidirectional"))
      (node (ref "IC4") (pin "8") (pinfunction "T4_8") (pintype "input"))
      (node (ref "R15") (pin "2") (pinfunction "2_2") (pintype "passive"))
    )
    (net (code "29") (name "/GPIO1A") (class "Default")
      (node (ref "D2") (pin "3") (pinfunction "C2_3") (pintype "passive"))
      (node (ref "IC3") (pin "40") (pinfunction "PE5_40") (pintype "bidirectional"))
      (node (ref "IC3") (pin "95") (pinfunction "PA0_95") (pintype "bidirectional"))
      (node (ref "PTC1") (pin "1") (pinfunction "1_1") (pintype "passive"))
    )
    (net (code "30") (name "/GPIO1B") (class "Default")
      (node (ref "D2") (pin "2") (pinfunction "C1_2") (pintype "passive"))
      (node (ref "IC3") (pin "39") (pinfunction "PE4_39") (pintype "bidirectional"))
      (node (ref "IC3") (pin "96") (pinfunction "PA1_96") (pintype "bidirectional"))
      (node (ref "PTC2") (pin "1") (pinfunction "1_1") (pintype "passive"))
    )
    (net (code "31") (name "/GPIO2A") (class "Default")
      (node (ref "D4") (pin "3") (pinfunction "C2_3") (pintype "passive"))
      (node (ref "IC3") (pin "36") (pinfunction "PE1_36") (pintype "bidirectional"))
      (node (ref "IC3") (pin "97") (pinfunction "PA2_97") (pintype "bidirectional"))
      (node (ref "PTC3") (pin "1") (pinfunction "1_1") (pintype "passive"))
    )
    (net (code "32") (name "/GPIO2B") (class "Default")
      (node (ref "D4") (pin "2") (pinfunction "C1_2") (pintype "passive"))
      (node (ref "IC3") (pin "35") (pinfunction "PE0_35") (pintype "bidirectional"))
      (node (ref "IC3") (pin "98") (pinfunction "PA3_98") (pintype "bidirectional"))
      (node (ref "PTC4") (pin "1") (pinfunction "1_1") (pintype "passive"))
    )
    (net (code "33") (name "/GPIO3A") (class "Default")
      (node (ref "D6") (pin "3") (pinfunction "C2_3") (pintype "passive"))
      (node (ref "IC3") (pin "30") (pinfunction "PD5_30") (pintype "bidirectional"))
      (node (ref "IC3") (pin "99") (pinfunction "PA4_99") (pintype "bidirectional"))
      (node (ref "PTC5") (pin "1") (pinfunction "1_1") (pintype "passive"))
    )
    (net (code "34") (name "/GPIO3B") (class "Default")
      (node (ref "D6") (pin "2") (pinfunction "C1_2") (pintype "passive"))
      (node (ref "IC3") (pin "100") (pinfunction "PA5_100") (pintype "bidirectional"))
      (node (ref "IC3") (pin "29") (pinfunction "PD4_29") (pintype "bidirectional"))
      (node (ref "PTC6") (pin "1") (pinfunction "1_1") (pintype "passive"))
    )
    (net (code "35") (name "/GPIO4A") (class "Default")
      (node (ref "D8") (pin "3") (pinfunction "C2_3") (pintype "passive"))
      (node (ref "IC3") (pin "1") (pinfunction "PA6_1") (pintype "bidirectional"))
      (node (ref "IC3") (pin "26") (pinfunction "PD1_26") (pintype "bidirectional"))
      (node (ref "PTC7") (pin "1") (pinfunction "1_1") (pintype "passive"))
    )
    (net (code "36") (name "/GPIO4B") (class "Default")
      (node (ref "D8") (pin "2") (pinfunction "C1_2") (pintype "passive"))
      (node (ref "IC3") (pin "2") (pinfunction "PA7_2") (pintype "bidirectional"))
      (node (ref "IC3") (pin "25") (pinfunction "PD0_25") (pintype "bidirectional"))
      (node (ref "PTC8") (pin "1") (pinfunction "1_1") (pintype "passive"))
    )
    (net (code "37") (name "/GPS_RXD") (class "Default")
      (node (ref "IC3") (pin "37") (pinfunction "PE2_37") (pintype "bidirectional"))
      (node (ref "U2") (pin "5") (pinfunction "TX_5") (pintype "bidirectional"))
    )
    (net (code "38") (name "/GPS_TXD") (class "Default")
      (node (ref "IC3") (pin "38") (pinfunction "PE3_38") (pintype "bidirectional"))
      (node (ref "U2") (pin "6") (pinfunction "RX_6") (pintype "bidirectional"))
    )
    (net (code "39") (name "/LED_STATUS") (class "Default")
      (node (ref "IC3") (pin "20") (pinfunction "PC5_20") (pintype "bidirectional"))
      (node (ref "LED1") (pin "C") (pinfunction "C_C") (pintype "passive"))
    )
    (net (code "40") (name "/MOT1_5V") (class "Default")
      (node (ref "JP1") (pin "3") (pinfunction "3_3") (pintype "passive"))
      (node (ref "X8") (pin "2") (pinfunction "S_2") (pintype "passive"))
    )
    (net (code "41") (name "/MOT1_A") (class "Default")
      (node (ref "B1") (pin "P$1") (pinfunction "S_P$1") (pintype "passive"))
      (node (ref "X1") (pin "1") (pinfunction "S_1") (pintype "passive"))
    )
    (net (code "42") (name "/MOT1_B") (class "Default")
      (node (ref "B2") (pin "P$1") (pinfunction "S_P$1") (pintype "passive"))
      (node (ref "X1") (pin "2") (pinfunction "S_2") (pintype "passive"))
    )
    (net (code "43") (name "/MOT1_C") (class "Default")
      (node (ref "B3") (pin "P$1") (pinfunction "S_P$1") (pintype "passive"))
      (node (ref "X1") (pin "3") (pinfunction "S_3") (pintype "passive"))
    )
    (net (code "44") (name "/MOT1_SIG") (class "Default")
      (node (ref "IC3") (pin "46") (pinfunction "PF1_46") (pintype "bidirectional"))
      (node (ref "X8") (pin "1") (pinfunction "S_1") (pintype "passive"))
    )
    (net (code "45") (name "/MOT2_5V") (class "Default")
      (node (ref "JP1") (pin "1") (pinfunction "1_1") (pintype "passive"))
      (node (ref "X9") (pin "2") (pinfunction "S_2") (pintype "passive"))
    )
    (net (code "46") (name "/MOT2_A") (class "Default")
      (node (ref "B4") (pin "P$1") (pinfunction "S_P$1") (pintype "passive"))
      (node (ref "X2") (pin "1") (pinfunction "S_1") (pintype "passive"))
    )
    (net (code "47") (name "/MOT2_B") (class "Default")
      (node (ref "B5") (pin "P$1") (pinfunction "S_P$1") (pintype "passive"))
      (node (ref "X2") (pin "2") (pinfunction "S_2") (pintype "passive"))
    )
    (net (code "48") (name "/MOT2_C") (class "Default")
      (node (ref "B6") (pin "P$1") (pinfunction "S_P$1") (pintype "passive"))
      (node (ref "X2") (pin "3") (pinfunction "S_3") (pintype "passive"))
    )
    (net (code "49") (name "/MOT2_SIG") (class "Default")
      (node (ref "IC3") (pin "45") (pinfunction "PF0_45") (pintype "bidirectional"))
      (node (ref "X9") (pin "1") (pinfunction "S_1") (pintype "passive"))
    )
    (net (code "50") (name "/PWR_CTL") (class "Default")
      (node (ref "IC3") (pin "68") (pinfunction "PJ3_68") (pintype "bidirectional"))
      (node (ref "R5") (pin "1") (pinfunction "1_1") (pintype "passive"))
    )
    (net (code "51") (name "/PWR_CTL1") (class "Default")
      (node (ref "IC3") (pin "81") (pinfunction "PK6_81") (pintype "bidirectional"))
      (node (ref "IC4") (pin "3") (pinfunction "IN1_3") (pintype "input"))
      (node (ref "R12") (pin "1") (pinfunction "1_1") (pintype "passive"))
    )
    (net (code "52") (name "/PWR_CTL2") (class "Default")
      (node (ref "IC3") (pin "79") (pinfunction "PK4_79") (pintype "bidirectional"))
      (node (ref "IC4") (pin "5") (pinfunction "IN2_5") (pintype "input"))
      (node (ref "R13") (pin "1") (pinfunction "1_1") (pintype "passive"))
    )
    (net (code "53") (name "/PWR_CTL3") (class "Default")
      (node (ref "IC3") (pin "77") (pinfunction "PK2_77") (pintype "bidirectional"))
      (node (ref "IC4") (pin "7") (pinfunction "IN3_7") (pintype "input"))
      (node (ref "R14") (pin "1") (pinfunction "1_1") (pintype "passive"))
    )
    (net (code "54") (name "/PWR_CTL4") (class "Default")
      (node (ref "IC3") (pin "75") (pinfunction "PK0_75") (pintype "bidirectional"))
      (node (ref "IC4") (pin "9") (pinfunction "IN4_9") (pintype "input"))
      (node (ref "R15") (pin "1") (pinfunction "1_1") (pintype "passive"))
    )
    (net (code "55") (name "/PWR_SENSE") (class "Default")
      (node (ref "D1") (pin "3") (pinfunction "C_3") (pintype "passive"))
      (node (ref "IC3") (pin "67") (pinfunction "PJ2_67") (pintype "bidirectional"))
      (node (ref "R6") (pin "1") (pinfunction "1_1") (pintype "passive"))
    )
    (net (code "56") (name "/RX1_TTL") (class "Default")
      (node (ref "IC1") (pin "9") (pinfunction "R1OUT_9") (pintype "output"))
      (node (ref "IC3") (pin "17") (pinfunction "PC2_17") (pintype "bidirectional"))
      (node (ref "IC6") (pin "4") (pinfunction "Y_4") (pintype "passive"))
    )
    (net (code "57") (name "/RX2_TTL") (class "Default")
      (node (ref "IC10") (pin "4") (pinfunction "Y_4") (pintype "passive"))
      (node (ref "IC3") (pin "21") (pinfunction "PC6_21") (pintype "bidirectional"))
      (node (ref "IC7") (pin "9") (pinfunction "R1OUT_9") (pintype "output"))
    )
    (net (code "58") (name "/RX3_TTL") (class "Default")
      (node (ref "IC11") (pin "9") (pinfunction "R1OUT_9") (pintype "output"))
      (node (ref "IC14") (pin "4") (pinfunction "Y_4") (pintype "passive"))
      (node (ref "IC3") (pin "31") (pinfunction "PD6_31") (pintype "bidirectional"))
    )
    (net (code "59") (name "/RX4_TTL") (class "Default")
      (node (ref "IC15") (pin "9") (pinfunction "R1OUT_9") (pintype "output"))
      (node (ref "IC18") (pin "4") (pinfunction "Y_4") (pintype "passive"))
      (node (ref "IC3") (pin "27") (pinfunction "PD2_27") (pintype "bidirectional"))
    )
    (net (code "60") (name "/S1_5V") (class "Default")
      (node (ref "IC5") (pin "5") (pinfunction "VCC_5") (pintype "passive"))
      (node (ref "PTC9") (pin "2") (pinfunction "2_2") (pintype "passive"))
      (node (ref "X4") (pin "4") (pinfunction "S_4") (pintype "passive"))
    )
    (net (code "61") (name "/S1_12V") (class "Default")
      (node (ref "T6") (pin "3") (pinfunction "S_3") (pintype "passive"))
      (node (ref "X4") (pin "1") (pinfunction "S_1") (pintype "passive"))
    )
    (net (code "62") (name "/S1_GPIO_A") (class "Default")
      (node (ref "PTC1") (pin "2") (pinfunction "2_2") (pintype "passive"))
      (node (ref "X4") (pin "5") (pinfunction "S_5") (pintype "passive"))
    )
    (net (code "63") (name "/S1_GPIO_B") (class "Default")
      (node (ref "PTC2") (pin "2") (pinfunction "2_2") (pintype "passive"))
      (node (ref "X4") (pin "6") (pinfunction "S_6") (pintype "passive"))
    )
    (net (code "64") (name "/S1_RX") (class "Default")
      (node (ref "IC1") (pin "8") (pinfunction "R1IN_8") (pintype "input"))
      (node (ref "R16") (pin "2") (pinfunction "2_2") (pintype "passive"))
      (node (ref "X4") (pin "2") (pinfunction "S_2") (pintype "passive"))
    )
    (net (code "65") (name "/S1_RX_33V") (class "Default")
      (node (ref "D3") (pin "3") (pinfunction "C2_3") (pintype "passive"))
      (node (ref "IC6") (pin "1") (pinfunction "A_1") (pintype "input"))
      (node (ref "R16") (pin "1") (pinfunction "1_1") (pintype "passive"))
    )
    (net (code "66") (name "/S1_TX") (class "Default")
      (node (ref "IC1") (pin "13") (pinfunction "T1OUT_13") (pintype "output"))
      (node (ref "IC5") (pin "4") (pinfunction "Y_4") (pintype "passive"))
      (node (ref "X4") (pin "3") (pinfunction "S_3") (pintype "passive"))
    )
    (net (code "67") (name "/S2_5V") (class "Default")
      (node (ref "IC9") (pin "5") (pinfunction "VCC_5") (pintype "passive"))
      (node (ref "PTC10") (pin "2") (pinfunction "2_2") (pintype "passive"))
      (node (ref "X5") (pin "4") (pinfunction "S_4") (pintype "passive"))
    )
    (net (code "68") (name "/S2_12V") (class "Default")
      (node (ref "T7") (pin "3") (pinfunction "S_3") (pintype "passive"))
      (node (ref "X5") (pin "1") (pinfunction "S_1") (pintype "passive"))
    )
    (net (code "69") (name "/S2_GPIO_A") (class "Default")
      (node (ref "PTC3") (pin "2") (pinfunction "2_2") (pintype "passive"))
      (node (ref "X5") (pin "5") (pinfunction "S_5") (pintype "passive"))
    )
    (net (code "70") (name "/S2_GPIO_B") (class "Default")
      (node (ref "PTC4") (pin "2") (pinfunction "2_2") (pintype "passive"))
      (node (ref "X5") (pin "6") (pinfunction "S_6") (pintype "passive"))
    )
    (net (code "71") (name "/S2_RX") (class "Default")
      (node (ref "IC7") (pin "8") (pinfunction "R1IN_8") (pintype "input"))
      (node (ref "R17") (pin "2") (pinfunction "2_2") (pintype "passive"))
      (node (ref "X5") (pin "2") (pinfunction "S_2") (pintype "passive"))
    )
    (net (code "72") (name "/S2_RX_33V") (class "Default")
      (node (ref "D3") (pin "2") (pinfunction "C1_2") (pintype "passive"))
      (node (ref "IC10") (pin "1") (pinfunction "A_1") (pintype "input"))
      (node (ref "R17") (pin "1") (pinfunction "1_1") (pintype "passive"))
    )
    (net (code "73") (name "/S2_TX") (class "Default")
      (node (ref "IC7") (pin "13") (pinfunction "T1OUT_13") (pintype "output"))
      (node (ref "IC9") (pin "4") (pinfunction "Y_4") (pintype "passive"))
      (node (ref "X5") (pin "3") (pinfunction "S_3") (pintype "passive"))
    )
    (net (code "74") (name "/S3_5V") (class "Default")
      (node (ref "IC13") (pin "5") (pinfunction "VCC_5") (pintype "passive"))
      (node (ref "PTC11") (pin "2") (pinfunction "2_2") (pintype "passive"))
      (node (ref "X6") (pin "4") (pinfunction "S_4") (pintype "passive"))
    )
    (net (code "75") (name "/S3_12V") (class "Default")
      (node (ref "T8") (pin "3") (pinfunction "S_3") (pintype "passive"))
      (node (ref "X6") (pin "1") (pinfunction "S_1") (pintype "passive"))
    )
    (net (code "76") (name "/S3_GPIO_A") (class "Default")
      (node (ref "PTC5") (pin "2") (pinfunction "2_2") (pintype "passive"))
      (node (ref "X6") (pin "5") (pinfunction "S_5") (pintype "passive"))
    )
    (net (code "77") (name "/S3_GPIO_B") (class "Default")
      (node (ref "PTC6") (pin "2") (pinfunction "2_2") (pintype "passive"))
      (node (ref "X6") (pin "6") (pinfunction "S_6") (pintype "passive"))
    )
    (net (code "78") (name "/S3_RX") (class "Default")
      (node (ref "IC11") (pin "8") (pinfunction "R1IN_8") (pintype "input"))
      (node (ref "R18") (pin "2") (pinfunction "2_2") (pintype "passive"))
      (node (ref "X6") (pin "2") (pinfunction "S_2") (pintype "passive"))
    )
    (net (code "79") (name "/S3_RX_33V") (class "Default")
      (node (ref "D7") (pin "3") (pinfunction "C2_3") (pintype "passive"))
      (node (ref "IC14") (pin "1") (pinfunction "A_1") (pintype "input"))
      (node (ref "R18") (pin "1") (pinfunction "1_1") (pintype "passive"))
    )
    (net (code "80") (name "/S3_TX") (class "Default")
      (node (ref "IC11") (pin "13") (pinfunction "T1OUT_13") (pintype "output"))
      (node (ref "IC13") (pin "4") (pinfunction "Y_4") (pintype "passive"))
      (node (ref "X6") (pin "3") (pinfunction "S_3") (pintype "passive"))
    )
    (net (code "81") (name "/S4_5V") (class "Default")
      (node (ref "IC17") (pin "5") (pinfunction "VCC_5") (pintype "passive"))
      (node (ref "PTC12") (pin "2") (pinfunction "2_2") (pintype "passive"))
      (node (ref "X7") (pin "4") (pinfunction "S_4") (pintype "passive"))
    )
    (net (code "82") (name "/S4_12V") (class "Default")
      (node (ref "T9") (pin "3") (pinfunction "S_3") (pintype "passive"))
      (node (ref "X7") (pin "1") (pinfunction "S_1") (pintype "passive"))
    )
    (net (code "83") (name "/S4_GPIO_A") (class "Default")
      (node (ref "PTC7") (pin "2") (pinfunction "2_2") (pintype "passive"))
      (node (ref "X7") (pin "5") (pinfunction "S_5") (pintype "passive"))
    )
    (net (code "84") (name "/S4_GPIO_B") (class "Default")
      (node (ref "PTC8") (pin "2") (pinfunction "2_2") (pintype "passive"))
      (node (ref "X7") (pin "6") (pinfunction "S_6") (pintype "passive"))
    )
    (net (code "85") (name "/S4_RX") (class "Default")
      (node (ref "IC15") (pin "8") (pinfunction "R1IN_8") (pintype "input"))
      (node (ref "R19") (pin "2") (pinfunction "2_2") (pintype "passive"))
      (node (ref "X7") (pin "2") (pinfunction "S_2") (pintype "passive"))
    )
    (net (code "86") (name "/S4_RX_33V") (class "Default")
      (node (ref "D7") (pin "2") (pinfunction "C1_2") (pintype "passive"))
      (node (ref "IC18") (pin "1") (pinfunction "A_1") (pintype "input"))
      (node (ref "R19") (pin "1") (pinfunction "1_1") (pintype "passive"))
    )
    (net (code "87") (name "/S4_TX") (class "Default")
      (node (ref "IC15") (pin "13") (pinfunction "T1OUT_13") (pintype "output"))
      (node (ref "IC17") (pin "4") (pinfunction "Y_4") (pintype "passive"))
      (node (ref "X7") (pin "3") (pinfunction "S_3") (pintype "passive"))
    )
    (net (code "88") (name "/TX1_TTL") (class "Default")
      (node (ref "IC1") (pin "11") (pinfunction "T1IN_11") (pintype "input"))
      (node (ref "IC3") (pin "18") (pinfunction "PC3_18") (pintype "bidirectional"))
      (node (ref "IC5") (pin "1") (pinfunction "A_1") (pintype "input"))
    )
    (net (code "89") (name "/TX2_TTL") (class "Default")
      (node (ref "IC3") (pin "22") (pinfunction "PC7_22") (pintype "bidirectional"))
      (node (ref "IC7") (pin "11") (pinfunction "T1IN_11") (pintype "input"))
      (node (ref "IC9") (pin "1") (pinfunction "A_1") (pintype "input"))
    )
    (net (code "90") (name "/TX3_TTL") (class "Default")
      (node (ref "IC11") (pin "11") (pinfunction "T1IN_11") (pintype "input"))
      (node (ref "IC13") (pin "1") (pinfunction "A_1") (pintype "input"))
      (node (ref "IC3") (pin "32") (pinfunction "PD7_32") (pintype "bidirectional"))
    )
    (net (code "91") (name "/TX4_TTL") (class "Default")
      (node (ref "IC15") (pin "11") (pinfunction "T1IN_11") (pintype "input"))
      (node (ref "IC17") (pin "1") (pinfunction "A_1") (pintype "input"))
      (node (ref "IC3") (pin "28") (pinfunction "PD3_28") (pintype "bidirectional"))
    )
    (net (code "92") (name "/USER_BUTTON") (class "Default")
      (node (ref "IC3") (pin "55") (pinfunction "PH0_55") (pintype "bidirectional"))
      (node (ref "S2") (pin "1") (pinfunction "1_1") (pintype "passive"))
    )
    (net (code "93") (name "/WATER_SENSE") (class "Default")
      (node (ref "R32") (pin "2") (pinfunction "2_2") (pintype "passive"))
      (node (ref "X18") (pin "1") (pinfunction "S_1") (pintype "passive"))
    )
    (net (code "94") (name "/~{CHRG_FAULT}") (class "Default")
      (node (ref "IC2") (pin "5") (pinfunction "~{FAULT}_5") (pintype "bidirectional"))
      (node (ref "IC3") (pin "65") (pinfunction "PJ0_65") (pintype "bidirectional"))
    )
    (net (code "95") (name "/~{CHRG}") (class "Default")
      (node (ref "IC2") (pin "4") (pinfunction "~{CHRG}_4") (pintype "bidirectional"))
      (node (ref "IC3") (pin "66") (pinfunction "PJ1_66") (pintype "bidirectional"))
    )
    (net (code "96") (name "/~{EN232_1}") (class "Default")
      (node (ref "IC1") (pin "1") (pinfunction "~{EN}_1") (pintype "input"))
      (node (ref "IC19") (pin "9") (pinfunction "I_9") (pintype "input"))
      (node (ref "IC3") (pin "69") (pinfunction "PJ4_69") (pintype "bidirectional"))
    )
    (net (code "97") (name "/~{EN232_2}") (class "Default")
      (node (ref "IC19") (pin "5") (pinfunction "I_5") (pintype "input"))
      (node (ref "IC3") (pin "70") (pinfunction "PJ5_70") (pintype "bidirectional"))
      (node (ref "IC7") (pin "1") (pinfunction "~{EN}_1") (pintype "input"))
    )
    (net (code "98") (name "/~{EN232_3}") (class "Default")
      (node (ref "IC11") (pin "1") (pinfunction "~{EN}_1") (pintype "input"))
      (node (ref "IC19") (pin "3") (pinfunction "I_3") (pintype "input"))
      (node (ref "IC3") (pin "71") (pinfunction "PJ6_71") (pintype "bidirectional"))
    )
    (net (code "99") (name "/~{EN232_4}") (class "Default")
      (node (ref "IC15") (pin "1") (pinfunction "~{EN}_1") (pintype "input"))
      (node (ref "IC19") (pin "1") (pinfunction "I_1") (pintype "input"))
      (node (ref "IC3") (pin "72") (pinfunction "PJ7_72") (pintype "bidirectional"))
    )
    (net (code "100") (name "GND") (class "Default")
      (node (ref "B8") (pin "P$1") (pinfunction "S_P$1") (pintype "passive"))
      (node (ref "C1") (pin "-") (pinfunction "-_-") (pintype "passive"))
      (node (ref "C10") (pin "2") (pinfunction "2_2") (pintype "passive"))
      (node (ref "C11") (pin "2") (pinfunction "2_2") (pintype "passive"))
      (node (ref "C12") (pin "2") (pinfunction "2_2") (pintype "passive"))
      (node (ref "C14") (pin "2") (pinfunction "2_2") (pintype "passive"))
      (node (ref "C15") (pin "2") (pinfunction "2_2") (pintype "passive"))
      (node (ref "C18") (pin "2") (pinfunction "2_2") (pintype "passive"))
      (node (ref "C19") (pin "1") (pinfunction "1_1") (pintype "passive"))
      (node (ref "C20") (pin "2") (pinfunction "2_2") (pintype "passive"))
      (node (ref "C21") (pin "2") (pinfunction "2_2") (pintype "passive"))
      (node (ref "C22") (pin "2") (pinfunction "2_2") (pintype "passive"))
      (node (ref "C25") (pin "2") (pinfunction "2_2") (pintype "passive"))
      (node (ref "C26") (pin "1") (pinfunction "1_1") (pintype "passive"))
      (node (ref "C27") (pin "2") (pinfunction "2_2") (pintype "passive"))
      (node (ref "C28") (pin "2") (pinfunction "2_2") (pintype "passive"))
      (node (ref "C29") (pin "-") (pinfunction "-_-") (pintype "passive"))
      (node (ref "C32") (pin "2") (pinfunction "2_2") (pintype "passive"))
      (node (ref "C33") (pin "1") (pinfunction "1_1") (pintype "passive"))
      (node (ref "C34") (pin "2") (pinfunction "2_2") (pintype "passive"))
      (node (ref "C37") (pin "2") (pinfunction "2_2") (pintype "passive"))
      (node (ref "C4") (pin "2") (pinfunction "2_2") (pintype "passive"))
      (node (ref "C41") (pin "2") (pinfunction "2_2") (pintype "passive"))
      (node (ref "C43") (pin "2") (pinfunction "2_2") (pintype "passive"))
      (node (ref "C44") (pin "2") (pinfunction "2_2") (pintype "passive"))
      (node (ref "C45") (pin "2") (pinfunction "2_2") (pintype "passive"))
      (node (ref "C46") (pin "2") (pinfunction "2_2") (pintype "passive"))
      (node (ref "C47") (pin "2") (pinfunction "2_2") (pintype "passive"))
      (node (ref "C48") (pin "2") (pinfunction "2_2") (pintype "passive"))
      (node (ref "C5") (pin "1") (pinfunction "1_1") (pintype "passive"))
      (node (ref "C6") (pin "2") (pinfunction "2_2") (pintype "passive"))
      (node (ref "C7") (pin "2") (pinfunction "2_2") (pintype "passive"))
      (node (ref "C8") (pin "-") (pinfunction "-_-") (pintype "passive"))
      (node (ref "C9") (pin "2") (pinfunction "2_2") (pintype "passive"))
      (node (ref "D1") (pin "1") (pinfunction "A_1") (pintype "passive"))
      (node (ref "D10") (pin "A") (pinfunction "A_A") (pintype "passive"))
      (node (ref "D2") (pin "1") (pinfunction "A_1") (pintype "passive"))
      (node (ref "D3") (pin "1") (pinfunction "A_1") (pintype "passive"))
      (node (ref "D4") (pin "1") (pinfunction "A_1") (pintype "passive"))
      (node (ref "D6") (pin "1") (pinfunction "A_1") (pintype "passive"))
      (node (ref "D7") (pin "1") (pinfunction "A_1") (pintype "passive"))
      (node (ref "D8") (pin "1") (pinfunction "A_1") (pintype "passive"))
      (node (ref "IC1") (pin "14") (pinfunction "GND_14") (pintype "power_in"))
      (node (ref "IC10") (pin "2") (pinfunction "GND_2") (pintype "power_in"))
      (node (ref "IC11") (pin "14") (pinfunction "GND_14") (pintype "power_in"))
      (node (ref "IC12") (pin "4") (pinfunction "GND_4") (pintype "power_in"))
      (node (ref "IC13") (pin "2") (pinfunction "GND_2") (pintype "power_in"))
      (node (ref "IC14") (pin "2") (pinfunction "GND_2") (pintype "power_in"))
      (node (ref "IC15") (pin "14") (pinfunction "GND_14") (pintype "power_in"))
      (node (ref "IC16") (pin "1") (pinfunction "GND_1") (pintype "passive"))
      (node (ref "IC17") (pin "2") (pinfunction "GND_2") (pintype "power_in"))
      (node (ref "IC18") (pin "2") (pinfunction "GND_2") (pintype "power_in"))
      (node (ref "IC19") (pin "11") (pinfunction "I_11") (pintype "input"))
      (node (ref "IC19") (pin "13") (pinfunction "I_13") (pintype "input"))
      (node (ref "IC19") (pin "7") (pinfunction "GND_7") (pintype "power_in"))
      (node (ref "IC2") (pin "13") (pinfunction "GND_13") (pintype "power_in"))
      (node (ref "IC3") (pin "13") (pinfunction "GND1_13") (pintype "power_in"))
      (node (ref "IC3") (pin "23") (pinfunction "GND2_23") (pintype "power_in"))
      (node (ref "IC3") (pin "3") (pinfunction "GND_3") (pintype "power_in"))
      (node (ref "IC3") (pin "33") (pinfunction "GND3_33") (pintype "power_in"))
      (node (ref "IC3") (pin "43") (pinfunction "GND4_43") (pintype "power_in"))
      (node (ref "IC3") (pin "53") (pinfunction "GND5_53") (pintype "power_in"))
      (node (ref "IC3") (pin "63") (pinfunction "GND6_63") (pintype "power_in"))
      (node (ref "IC3") (pin "73") (pinfunction "GND7_73") (pintype "power_in"))
      (node (ref "IC3") (pin "84") (pinfunction "GND8_84") (pintype "power_in"))
      (node (ref "IC3") (pin "93") (pinfunction "GND9_93") (pintype "power_in"))
      (node (ref "IC4") (pin "1") (pinfunction "GND_1") (pintype "input"))
      (node (ref "IC4") (pin "10") (pinfunction "GND1_10") (pintype "input"))
      (node (ref "IC5") (pin "2") (pinfunction "GND_2") (pintype "power_in"))
      (node (ref "IC6") (pin "2") (pinfunction "GND_2") (pintype "power_in"))
      (node (ref "IC7") (pin "14") (pinfunction "GND_14") (pintype "power_in"))
      (node (ref "IC8") (pin "4") (pinfunction "GND_4") (pintype "power_in"))
      (node (ref "IC9") (pin "2") (pinfunction "GND_2") (pintype "power_in"))
      (node (ref "ISP1") (pin "6") (pinfunction "6_6") (pintype "passive"))
      (node (ref "R23") (pin "1") (pinfunction "1_1") (pintype "passive"))
      (node (ref "R24") (pin "1") (pinfunction "1_1") (pintype "passive"))
      (node (ref "R25") (pin "1") (pinfunction "1_1") (pintype "passive"))
      (node (ref "R26") (pin "1") (pinfunction "1_1") (pintype "passive"))
      (node (ref "R27") (pin "1") (pinfunction "1_1") (pintype "passive"))
      (node (ref "R30") (pin "1") (pinfunction "1_1") (pintype "passive"))
      (node (ref "S1") (pin "2") (pinfunction "2_2") (pintype "passive"))
      (node (ref "S2") (pin "2") (pinfunction "2_2") (pintype "passive"))
      (node (ref "T1") (pin "1") (pinfunction "C_1") (pintype "passive"))
      (node (ref "U1") (pin "1") (pinfunction "GND_1") (pintype "bidirectional"))
      (node (ref "U1") (pin "12") (pinfunction "GND1_12") (pintype "bidirectional"))
      (node (ref "U1") (pin "25") (pinfunction "GND2_25") (pintype "bidirectional"))
      (node (ref "U1") (pin "27") (pinfunction "GND3_27") (pintype "bidirectional"))
      (node (ref "U1") (pin "28") (pinfunction "GND4_28") (pintype "bidirectional"))
      (node (ref "U1") (pin "29") (pinfunction "GND5_29") (pintype "bidirectional"))
      (node (ref "U2") (pin "4") (pinfunction "GND_4") (pintype "bidirectional"))
      (node (ref "X10") (pin "NEG") (pinfunction "S_NEG") (pintype "passive"))
      (node (ref "X11") (pin "1") (pinfunction "1_1") (pintype "passive"))
      (node (ref "X12") (pin "NEG") (pinfunction "S_NEG") (pintype "passive"))
      (node (ref "X13") (pin "1") (pinfunction "1_1") (pintype "passive"))
      (node (ref "X14") (pin "2") (pinfunction "S_2") (pintype "passive"))
      (node (ref "X15") (pin "NEG") (pinfunction "S_NEG") (pintype "passive"))
      (node (ref "X16") (pin "NEG") (pinfunction "S_NEG") (pintype "passive"))
      (node (ref "X17") (pin "4") (pinfunction "S_4") (pintype "passive"))
      (node (ref "X18") (pin "2") (pinfunction "S_2") (pintype "passive"))
      (node (ref "X3") (pin "2") (pinfunction "S_2") (pintype "passive"))
      (node (ref "X4") (pin "7") (pinfunction "S_7") (pintype "passive"))
      (node (ref "X5") (pin "7") (pinfunction "S_7") (pintype "passive"))
      (node (ref "X6") (pin "7") (pinfunction "S_7") (pintype "passive"))
      (node (ref "X7") (pin "7") (pinfunction "S_7") (pintype "passive"))
      (node (ref "X8") (pin "3") (pinfunction "S_3") (pintype "passive"))
      (node (ref "X9") (pin "3") (pinfunction "S_3") (pintype "passive"))
    )
    (net (code "101") (name "Net-(IC1A-C1+)") (class "Default")
      (node (ref "C2") (pin "1") (pinfunction "1_1") (pintype "passive"))
      (node (ref "IC1") (pin "2") (pinfunction "C1+_2") (pintype "passive"))
    )
    (net (code "102") (name "Net-(IC1A-C1-)") (class "Default")
      (node (ref "C2") (pin "2") (pinfunction "2_2") (pintype "passive"))
      (node (ref "IC1") (pin "4") (pinfunction "C1-_4") (pintype "passive"))
    )
    (net (code "103") (name "Net-(IC1A-C2+)") (class "Default")
      (node (ref "C3") (pin "1") (pinfunction "1_1") (pintype "passive"))
      (node (ref "IC1") (pin "5") (pinfunction "C2+_5") (pintype "passive"))
    )
    (net (code "104") (name "Net-(IC1A-C2-)") (class "Default")
      (node (ref "C3") (pin "2") (pinfunction "2_2") (pintype "passive"))
      (node (ref "IC1") (pin "6") (pinfunction "C2-_6") (pintype "passive"))
    )
    (net (code "105") (name "Net-(IC1A-V+)") (class "Default")
      (node (ref "C4") (pin "1") (pinfunction "1_1") (pintype "passive"))
      (node (ref "IC1") (pin "3") (pinfunction "V+_3") (pintype "passive"))
    )
    (net (code "106") (name "Net-(IC1A-V-)") (class "Default")
      (node (ref "C5") (pin "2") (pinfunction "2_2") (pintype "passive"))
      (node (ref "IC1") (pin "7") (pinfunction "V-_7") (pintype "passive"))
    )
    (net (code "107") (name "Net-(IC2-BOOST)") (class "Default")
      (node (ref "C42") (pin "2") (pinfunction "2_2") (pintype "passive"))
      (node (ref "D9") (pin "C") (pinfunction "C_C") (pintype "passive"))
      (node (ref "IC2") (pin "11") (pinfunction "BOOST_11") (pintype "output"))
    )
    (net (code "108") (name "Net-(IC2-SW)") (class "Default")
      (node (ref "C42") (pin "1") (pinfunction "1_1") (pintype "passive"))
      (node (ref "D10") (pin "C") (pinfunction "C_C") (pintype "passive"))
      (node (ref "IC2") (pin "12") (pinfunction "SW_12") (pintype "input"))
      (node (ref "L1") (pin "1") (pinfunction "1_1") (pintype "passive"))
    )
    (net (code "109") (name "Net-(IC2-TIMER)") (class "Default")
      (node (ref "C41") (pin "1") (pinfunction "1_1") (pintype "passive"))
      (node (ref "IC2") (pin "6") (pinfunction "TIMER_6") (pintype "bidirectional"))
    )
    (net (code "110") (name "Net-(IC2-VFB)") (class "Default")
      (node (ref "IC2") (pin "7") (pinfunction "VFB_7") (pintype "bidirectional"))
      (node (ref "R22") (pin "1") (pinfunction "1_1") (pintype "passive"))
      (node (ref "R24") (pin "2") (pinfunction "2_2") (pintype "passive"))
    )
    (net (code "111") (name "Net-(IC2-VIN)") (class "Default")
      (node (ref "C29") (pin "+") (pinfunction "+_+") (pintype "passive"))
      (node (ref "C7") (pin "1") (pinfunction "1_1") (pintype "passive"))
      (node (ref "D12") (pin "C") (pinfunction "C_C") (pintype "passive"))
      (node (ref "IC2") (pin "1") (pinfunction "VIN_1") (pintype "power_in"))
      (node (ref "IC2") (pin "2") (pinfunction "VREG_2") (pintype "input"))
      (node (ref "IC2") (pin "3") (pinfunction "~{SHDN}_3") (pintype "bidirectional"))
    )
    (net (code "112") (name "Net-(IC3-PB5)") (class "Default")
      (node (ref "IC3") (pin "10") (pinfunction "PB5_10") (pintype "bidirectional"))
      (node (ref "R32") (pin "1") (pinfunction "1_1") (pintype "passive"))
    )
    (net (code "113") (name "Net-(IC3-PDI_DATA)") (class "Default")
      (node (ref "IC3") (pin "89") (pinfunction "PDI_DATA_89") (pintype "bidirectional"))
      (node (ref "ISP1") (pin "1") (pinfunction "1_1") (pintype "passive"))
    )
    (net (code "114") (name "Net-(IC3-~{RESET}{slash}PDI_CLK)") (class "Default")
      (node (ref "IC3") (pin "90") (pinfunction "~{RESET}/PDI_CLK_90") (pintype "input"))
      (node (ref "ISP1") (pin "5") (pinfunction "5_5") (pintype "passive"))
      (node (ref "R2") (pin "1") (pinfunction "1_1") (pintype "passive"))
    )
    (net (code "115") (name "Net-(IC4-DS1)") (class "Default")
      (node (ref "IC4") (pin "19") (pinfunction "DS1_19") (pintype "output"))
      (node (ref "R8") (pin "1") (pinfunction "1_1") (pintype "passive"))
      (node (ref "T6") (pin "1") (pinfunction "D_1") (pintype "passive"))
      (node (ref "T6") (pin "2") (pinfunction "D1_2") (pintype "passive"))
      (node (ref "T6") (pin "5") (pinfunction "D2_5") (pintype "passive"))
      (node (ref "T6") (pin "6") (pinfunction "D3_6") (pintype "passive"))
    )
    (net (code "116") (name "Net-(IC4-DS2)") (class "Default")
      (node (ref "IC4") (pin "17") (pinfunction "DS2_17") (pintype "input"))
      (node (ref "R9") (pin "1") (pinfunction "1_1") (pintype "passive"))
      (node (ref "T7") (pin "1") (pinfunction "D_1") (pintype "passive"))
      (node (ref "T7") (pin "2") (pinfunction "D1_2") (pintype "passive"))
      (node (ref "T7") (pin "5") (pinfunction "D2_5") (pintype "passive"))
      (node (ref "T7") (pin "6") (pinfunction "D3_6") (pintype "passive"))
    )
    (net (code "117") (name "Net-(IC4-DS3)") (class "Default")
      (node (ref "IC4") (pin "15") (pinfunction "DS3_15") (pintype "output"))
      (node (ref "R10") (pin "1") (pinfunction "1_1") (pintype "passive"))
      (node (ref "T8") (pin "1") (pinfunction "D_1") (pintype "passive"))
      (node (ref "T8") (pin "2") (pinfunction "D1_2") (pintype "passive"))
      (node (ref "T8") (pin "5") (pinfunction "D2_5") (pintype "passive"))
      (node (ref "T8") (pin "6") (pinfunction "D3_6") (pintype "passive"))
    )
    (net (code "118") (name "Net-(IC4-DS4)") (class "Default")
      (node (ref "IC4") (pin "13") (pinfunction "DS4_13") (pintype "output"))
      (node (ref "R11") (pin "1") (pinfunction "1_1") (pintype "passive"))
      (node (ref "T9") (pin "1") (pinfunction "D_1") (pintype "passive"))
      (node (ref "T9") (pin "2") (pinfunction "D1_2") (pintype "passive"))
      (node (ref "T9") (pin "5") (pinfunction "D2_5") (pintype "passive"))
      (node (ref "T9") (pin "6") (pinfunction "D3_6") (pintype "passive"))
    )
    (net (code "119") (name "Net-(IC4-G1)") (class "Default")
      (node (ref "IC4") (pin "18") (pinfunction "G1_18") (pintype "output"))
      (node (ref "T6") (pin "4") (pinfunction "G_4") (pintype "passive"))
    )
    (net (code "120") (name "Net-(IC4-G2)") (class "Default")
      (node (ref "IC4") (pin "16") (pinfunction "G2_16") (pintype "output"))
      (node (ref "T7") (pin "4") (pinfunction "G_4") (pintype "passive"))
    )
    (net (code "121") (name "Net-(IC4-G3)") (class "Default")
      (node (ref "IC4") (pin "14") (pinfunction "G3_14") (pintype "input"))
      (node (ref "T8") (pin "4") (pinfunction "G_4") (pintype "passive"))
    )
    (net (code "122") (name "Net-(IC4-G4)") (class "Default")
      (node (ref "IC4") (pin "12") (pinfunction "G4_12") (pintype "output"))
      (node (ref "T9") (pin "4") (pinfunction "G_4") (pintype "passive"))
    )
    (net (code "123") (name "Net-(IC7A-C1+)") (class "Default")
      (node (ref "C16") (pin "1") (pinfunction "1_1") (pintype "passive"))
      (node (ref "IC7") (pin "2") (pinfunction "C1+_2") (pintype "passive"))
    )
    (net (code "124") (name "Net-(IC7A-C1-)") (class "Default")
      (node (ref "C16") (pin "2") (pinfunction "2_2") (pintype "passive"))
      (node (ref "IC7") (pin "4") (pinfunction "C1-_4") (pintype "passive"))
    )
    (net (code "125") (name "Net-(IC7A-C2+)") (class "Default")
      (node (ref "C17") (pin "1") (pinfunction "1_1") (pintype "passive"))
      (node (ref "IC7") (pin "5") (pinfunction "C2+_5") (pintype "passive"))
    )
    (net (code "126") (name "Net-(IC7A-C2-)") (class "Default")
      (node (ref "C17") (pin "2") (pinfunction "2_2") (pintype "passive"))
      (node (ref "IC7") (pin "6") (pinfunction "C2-_6") (pintype "passive"))
    )
    (net (code "127") (name "Net-(IC7A-V+)") (class "Default")
      (node (ref "C18") (pin "1") (pinfunction "1_1") (pintype "passive"))
      (node (ref "IC7") (pin "3") (pinfunction "V+_3") (pintype "passive"))
    )
    (net (code "128") (name "Net-(IC7A-V-)") (class "Default")
      (node (ref "C19") (pin "2") (pinfunction "2_2") (pintype "passive"))
      (node (ref "IC7") (pin "7") (pinfunction "V-_7") (pintype "passive"))
    )
    (net (code "129") (name "Net-(IC8-R_OS)") (class "Default")
      (node (ref "IC8") (pin "5") (pinfunction "R_OS_5") (pintype "input"))
      (node (ref "R26") (pin "2") (pinfunction "2_2") (pintype "passive"))
    )
    (net (code "130") (name "Net-(IC11A-C1+)") (class "Default")
      (node (ref "C23") (pin "1") (pinfunction "1_1") (pintype "passive"))
      (node (ref "IC11") (pin "2") (pinfunction "C1+_2") (pintype "passive"))
    )
    (net (code "131") (name "Net-(IC11A-C1-)") (class "Default")
      (node (ref "C23") (pin "2") (pinfunction "2_2") (pintype "passive"))
      (node (ref "IC11") (pin "4") (pinfunction "C1-_4") (pintype "passive"))
    )
    (net (code "132") (name "Net-(IC11A-C2+)") (class "Default")
      (node (ref "C24") (pin "1") (pinfunction "1_1") (pintype "passive"))
      (node (ref "IC11") (pin "5") (pinfunction "C2+_5") (pintype "passive"))
    )
    (net (code "133") (name "Net-(IC11A-C2-)") (class "Default")
      (node (ref "C24") (pin "2") (pinfunction "2_2") (pintype "passive"))
      (node (ref "IC11") (pin "6") (pinfunction "C2-_6") (pintype "passive"))
    )
    (net (code "134") (name "Net-(IC11A-V+)") (class "Default")
      (node (ref "C25") (pin "1") (pinfunction "1_1") (pintype "passive"))
      (node (ref "IC11") (pin "3") (pinfunction "V+_3") (pintype "passive"))
    )
    (net (code "135") (name "Net-(IC11A-V-)") (class "Default")
      (node (ref "C26") (pin "2") (pinfunction "2_2") (pintype "passive"))
      (node (ref "IC11") (pin "7") (pinfunction "V-_7") (pintype "passive"))
    )
    (net (code "136") (name "Net-(IC12-R_OS)") (class "Default")
      (node (ref "IC12") (pin "5") (pinfunction "R_OS_5") (pintype "input"))
      (node (ref "R27") (pin "2") (pinfunction "2_2") (pintype "passive"))
    )
    (net (code "137") (name "Net-(IC15A-C1+)") (class "Default")
      (node (ref "C30") (pin "1") (pinfunction "1_1") (pintype "passive"))
      (node (ref "IC15") (pin "2") (pinfunction "C1+_2") (pintype "passive"))
    )
    (net (code "138") (name "Net-(IC15A-C1-)") (class "Default")
      (node (ref "C30") (pin "2") (pinfunction "2_2") (pintype "passive"))
      (node (ref "IC15") (pin "4") (pinfunction "C1-_4") (pintype "passive"))
    )
    (net (code "139") (name "Net-(IC15A-C2+)") (class "Default")
      (node (ref "C31") (pin "1") (pinfunction "1_1") (pintype "passive"))
      (node (ref "IC15") (pin "5") (pinfunction "C2+_5") (pintype "passive"))
    )
    (net (code "140") (name "Net-(IC15A-C2-)") (class "Default")
      (node (ref "C31") (pin "2") (pinfunction "2_2") (pintype "passive"))
      (node (ref "IC15") (pin "6") (pinfunction "C2-_6") (pintype "passive"))
    )
    (net (code "141") (name "Net-(IC15A-V+)") (class "Default")
      (node (ref "C32") (pin "1") (pinfunction "1_1") (pintype "passive"))
      (node (ref "IC15") (pin "3") (pinfunction "V+_3") (pintype "passive"))
    )
    (net (code "142") (name "Net-(IC15A-V-)") (class "Default")
      (node (ref "C33") (pin "2") (pinfunction "2_2") (pintype "passive"))
      (node (ref "IC15") (pin "7") (pinfunction "V-_7") (pintype "passive"))
    )
    (net (code "143") (name "Net-(LED1-PadA)") (class "Default")
      (node (ref "LED1") (pin "A") (pinfunction "A_A") (pintype "passive"))
      (node (ref "R3") (pin "1") (pinfunction "1_1") (pintype "passive"))
    )
    (net (code "144") (name "Net-(LED2-PadA)") (class "Default")
      (node (ref "LED2") (pin "A") (pinfunction "A_A") (pintype "passive"))
      (node (ref "R7") (pin "1") (pinfunction "1_1") (pintype "passive"))
    )
    (net (code "145") (name "Net-(LED3-PadA)") (class "Default")
      (node (ref "LED3") (pin "A") (pinfunction "A_A") (pintype "passive"))
      (node (ref "R28") (pin "1") (pinfunction "1_1") (pintype "passive"))
    )
    (net (code "146") (name "Net-(Q1-G)") (class "Default")
      (node (ref "C13") (pin "2") (pinfunction "2_2") (pintype "passive"))
      (node (ref "Q1") (pin "1") (pinfunction "G_1") (pintype "passive"))
      (node (ref "R4") (pin "1") (pinfunction "1_1") (pintype "passive"))
      (node (ref "R6") (pin "2") (pinfunction "2_2") (pintype "passive"))
      (node (ref "S1") (pin "1") (pinfunction "1_1") (pintype "passive"))
      (node (ref "T1") (pin "2") (pinfunction "E_2") (pintype "passive"))
    )
    (net (code "147") (name "Net-(T1-B)") (class "Default")
      (node (ref "R5") (pin "2") (pinfunction "2_2") (pintype "passive"))
      (node (ref "T1") (pin "3") (pinfunction "B_3") (pintype "passive"))
    )
    (net (code "148") (name "Net-(U1-PIO5)") (class "Default")
      (node (ref "LED2") (pin "C") (pinfunction "C_C") (pintype "passive"))
      (node (ref "U1") (pin "21") (pinfunction "PIO5_21") (pintype "bidirectional"))
    )
    (net (code "149") (name "Net-(U2-LED)") (class "Default")
      (node (ref "LED3") (pin "C") (pinfunction "C_C") (pintype "passive"))
      (node (ref "U2") (pin "1") (pinfunction "LED_1") (pintype "bidirectional"))
    )
    (net (code "150") (name "Net-(X13B-1)") (class "Default")
      (node (ref "R31") (pin "1") (pinfunction "1_1") (pintype "passive"))
      (node (ref "X13") (pin "2") (pinfunction "1_2") (pintype "passive"))
    )
    (net (code "151") (name "Net-(X13C-1)") (class "Default")
      (node (ref "R1") (pin "1") (pinfunction "1_1") (pintype "passive"))
      (node (ref "X13") (pin "3") (pinfunction "1_3") (pintype "passive"))
    )
    (net (code "152") (name "Net-(X17A-S)") (class "Default")
      (node (ref "X17") (pin "2") (pinfunction "S_2") (pintype "passive"))
      (node (ref "X17") (pin "3") (pinfunction "S_3") (pintype "passive"))
    )
    (net (code "153") (name "Net-(X17C-S)") (class "Default")
      (node (ref "C15") (pin "1") (pinfunction "1_1") (pintype "passive"))
      (node (ref "L4") (pin "1") (pinfunction "1_1") (pintype "passive"))
      (node (ref "X17") (pin "1") (pinfunction "S_1") (pintype "passive"))
    )
    (net (code "154") (name "V+") (class "Default")
      (node (ref "C13") (pin "1") (pinfunction "1_1") (pintype "passive"))
      (node (ref "IC12") (pin "1") (pinfunction "VIN-_1") (pintype "passive"))
      (node (ref "Q1") (pin "2") (pinfunction "S_2") (pintype "passive"))
      (node (ref "R21") (pin "2") (pinfunction "2_2") (pintype "passive"))
      (node (ref "R4") (pin "2") (pinfunction "2_2") (pintype "passive"))
    )
    (net (code "155") (name "unconnected-(IC1A-FORCEON-Pad12)") (class "Default")
      (node (ref "IC1") (pin "12") (pinfunction "FORCEON_12") (pintype "input"))
    )
    (net (code "156") (name "unconnected-(IC1A-~{INVALID}-Pad10)") (class "Default")
      (node (ref "IC1") (pin "10") (pinfunction "~{INVALID}_10") (pintype "input"))
    )
    (net (code "157") (name "unconnected-(IC3-PB0-Pad5)") (class "Default")
      (node (ref "IC3") (pin "5") (pinfunction "PB0_5") (pintype "bidirectional"))
    )
    (net (code "158") (name "unconnected-(IC3-PB1-Pad6)") (class "Default")
      (node (ref "IC3") (pin "6") (pinfunction "PB1_6") (pintype "bidirectional"))
    )
    (net (code "159") (name "unconnected-(IC3-PB2-Pad7)") (class "Default")
      (node (ref "IC3") (pin "7") (pinfunction "PB2_7") (pintype "bidirectional"))
    )
    (net (code "160") (name "unconnected-(IC3-PC0-Pad15)") (class "Default")
      (node (ref "IC3") (pin "15") (pinfunction "PC0_15") (pintype "bidirectional"))
    )
    (net (code "161") (name "unconnected-(IC3-PC1-Pad16)") (class "Default")
      (node (ref "IC3") (pin "16") (pinfunction "PC1_16") (pintype "bidirectional"))
    )
    (net (code "162") (name "unconnected-(IC3-PC4-Pad19)") (class "Default")
      (node (ref "IC3") (pin "19") (pinfunction "PC4_19") (pintype "bidirectional"))
    )
    (net (code "163") (name "unconnected-(IC3-PF2-Pad47)") (class "Default")
      (node (ref "IC3") (pin "47") (pinfunction "PF2_47") (pintype "bidirectional"))
    )
    (net (code "164") (name "unconnected-(IC3-PF3-Pad48)") (class "Default")
      (node (ref "IC3") (pin "48") (pinfunction "PF3_48") (pintype "bidirectional"))
    )
    (net (code "165") (name "unconnected-(IC3-PH1-Pad56)") (class "Default")
      (node (ref "IC3") (pin "56") (pinfunction "PH1_56") (pintype "bidirectional"))
    )
    (net (code "166") (name "unconnected-(IC3-PH2-Pad57)") (class "Default")
      (node (ref "IC3") (pin "57") (pinfunction "PH2_57") (pintype "bidirectional"))
    )
    (net (code "167") (name "unconnected-(IC3-PH3-Pad58)") (class "Default")
      (node (ref "IC3") (pin "58") (pinfunction "PH3_58") (pintype "bidirectional"))
    )
    (net (code "168") (name "unconnected-(IC3-PH4-Pad59)") (class "Default")
      (node (ref "IC3") (pin "59") (pinfunction "PH4_59") (pintype "bidirectional"))
    )
    (net (code "169") (name "unconnected-(IC3-PH5-Pad60)") (class "Default")
      (node (ref "IC3") (pin "60") (pinfunction "PH5_60") (pintype "bidirectional"))
    )
    (net (code "170") (name "unconnected-(IC3-PH6-Pad61)") (class "Default")
      (node (ref "IC3") (pin "61") (pinfunction "PH6_61") (pintype "bidirectional"))
    )
    (net (code "171") (name "unconnected-(IC3-PH7-Pad62)") (class "Default")
      (node (ref "IC3") (pin "62") (pinfunction "PH7_62") (pintype "bidirectional"))
    )
    (net (code "172") (name "unconnected-(IC3-PQ0-Pad85)") (class "Default")
      (node (ref "IC3") (pin "85") (pinfunction "PQ0_85") (pintype "bidirectional"))
    )
    (net (code "173") (name "unconnected-(IC3-PQ1-Pad86)") (class "Default")
      (node (ref "IC3") (pin "86") (pinfunction "PQ1_86") (pintype "bidirectional"))
    )
    (net (code "174") (name "unconnected-(IC3-PQ2-Pad87)") (class "Default")
      (node (ref "IC3") (pin "87") (pinfunction "PQ2_87") (pintype "bidirectional"))
    )
    (net (code "175") (name "unconnected-(IC3-PQ3-Pad88)") (class "Default")
      (node (ref "IC3") (pin "88") (pinfunction "PQ3_88") (pintype "bidirectional"))
    )
    (net (code "176") (name "unconnected-(IC3-PR0(XT2)-Pad91)") (class "Default")
      (node (ref "IC3") (pin "91") (pinfunction "PR0(XT2)_91") (pintype "bidirectional"))
    )
    (net (code "177") (name "unconnected-(IC3-PR1(XT1)-Pad92)") (class "Default")
      (node (ref "IC3") (pin "92") (pinfunction "PR1(XT1)_92") (pintype "bidirectional"))
    )
    (net (code "178") (name "unconnected-(IC7A-FORCEON-Pad12)") (class "Default")
      (node (ref "IC7") (pin "12") (pinfunction "FORCEON_12") (pintype "input"))
    )
    (net (code "179") (name "unconnected-(IC7A-~{INVALID}-Pad10)") (class "Default")
      (node (ref "IC7") (pin "10") (pinfunction "~{INVALID}_10") (pintype "input"))
    )
    (net (code "180") (name "unconnected-(IC8-NC-Pad7)") (class "Default")
      (node (ref "IC8") (pin "7") (pinfunction "NC_7") (pintype "passive"))
    )
    (net (code "181") (name "unconnected-(IC11A-FORCEON-Pad12)") (class "Default")
      (node (ref "IC11") (pin "12") (pinfunction "FORCEON_12") (pintype "input"))
    )
    (net (code "182") (name "unconnected-(IC11A-~{INVALID}-Pad10)") (class "Default")
      (node (ref "IC11") (pin "10") (pinfunction "~{INVALID}_10") (pintype "input"))
    )
    (net (code "183") (name "unconnected-(IC12-NC-Pad7)") (class "Default")
      (node (ref "IC12") (pin "7") (pinfunction "NC_7") (pintype "passive"))
    )
    (net (code "184") (name "unconnected-(IC15A-FORCEON-Pad12)") (class "Default")
      (node (ref "IC15") (pin "12") (pinfunction "FORCEON_12") (pintype "input"))
    )
    (net (code "185") (name "unconnected-(IC15A-~{INVALID}-Pad10)") (class "Default")
      (node (ref "IC15") (pin "10") (pinfunction "~{INVALID}_10") (pintype "input"))
    )
    (net (code "186") (name "unconnected-(IC19E-O-Pad10)") (class "Default")
      (node (ref "IC19") (pin "10") (pinfunction "O_10") (pintype "output"))
    )
    (net (code "187") (name "unconnected-(IC19F-O-Pad12)") (class "Default")
      (node (ref "IC19") (pin "12") (pinfunction "O_12") (pintype "output"))
    )
    (net (code "188") (name "unconnected-(U1-AIO1-Pad35)") (class "Default")
      (node (ref "U1") (pin "35") (pinfunction "AIO1_35") (pintype "bidirectional"))
    )
    (net (code "189") (name "unconnected-(U1-AIO2-Pad30)") (class "Default")
      (node (ref "U1") (pin "30") (pinfunction "AIO2_30") (pintype "bidirectional"))
    )
    (net (code "190") (name "unconnected-(U1-NC-Pad26)") (class "Default")
      (node (ref "U1") (pin "26") (pinfunction "NC_26") (pintype "bidirectional"))
    )
    (net (code "191") (name "unconnected-(U1-PCMCLK-Pad7)") (class "Default")
      (node (ref "U1") (pin "7") (pinfunction "PCMCLK_7") (pintype "bidirectional"))
    )
    (net (code "192") (name "unconnected-(U1-PCMIN-Pad9)") (class "Default")
      (node (ref "U1") (pin "9") (pinfunction "PCMIN_9") (pintype "bidirectional"))
    )
    (net (code "193") (name "unconnected-(U1-PCMOUT-Pad10)") (class "Default")
      (node (ref "U1") (pin "10") (pinfunction "PCMOUT_10") (pintype "bidirectional"))
    )
    (net (code "194") (name "unconnected-(U1-PCMSYNC-Pad8)") (class "Default")
      (node (ref "U1") (pin "8") (pinfunction "PCMSYNC_8") (pintype "bidirectional"))
    )
    (net (code "195") (name "unconnected-(U1-PIO3-Pad20)") (class "Default")
      (node (ref "U1") (pin "20") (pinfunction "PIO3_20") (pintype "bidirectional"))
    )
    (net (code "196") (name "unconnected-(U1-PIO4-Pad22)") (class "Default")
      (node (ref "U1") (pin "22") (pinfunction "PIO4_22") (pintype "bidirectional"))
    )
    (net (code "197") (name "unconnected-(U1-PIO6-Pad3)") (class "Default")
      (node (ref "U1") (pin "3") (pinfunction "PIO6_3") (pintype "bidirectional"))
    )
    (net (code "198") (name "unconnected-(U1-PIO7-Pad4)") (class "Default")
      (node (ref "U1") (pin "4") (pinfunction "PIO7_4") (pintype "bidirectional"))
    )
    (net (code "199") (name "unconnected-(U1-PIO8-Pad31)") (class "Default")
      (node (ref "U1") (pin "31") (pinfunction "PIO8_31") (pintype "bidirectional"))
    )
    (net (code "200") (name "unconnected-(U1-PIO9-Pad32)") (class "Default")
      (node (ref "U1") (pin "32") (pinfunction "PIO9_32") (pintype "bidirectional"))
    )
    (net (code "201") (name "unconnected-(U1-PIO10-Pad33)") (class "Default")
      (node (ref "U1") (pin "33") (pinfunction "PIO10_33") (pintype "bidirectional"))
    )
    (net (code "202") (name "unconnected-(U1-PIO11-Pad34)") (class "Default")
      (node (ref "U1") (pin "34") (pinfunction "PIO11_34") (pintype "bidirectional"))
    )
    (net (code "203") (name "unconnected-(U1-SPICLK-Pad6)") (class "Default")
      (node (ref "U1") (pin "6") (pinfunction "SPICLK_6") (pintype "bidirectional"))
    )
    (net (code "204") (name "unconnected-(U1-SPICSB-Pad23)") (class "Default")
      (node (ref "U1") (pin "23") (pinfunction "SPICSB_23") (pintype "bidirectional"))
    )
    (net (code "205") (name "unconnected-(U1-SPIMISO-Pad24)") (class "Default")
      (node (ref "U1") (pin "24") (pinfunction "SPIMISO_24") (pintype "bidirectional"))
    )
    (net (code "206") (name "unconnected-(U1-SPIMOSI-Pad2)") (class "Default")
      (node (ref "U1") (pin "2") (pinfunction "SPIMOSI_2") (pintype "bidirectional"))
    )
    (net (code "207") (name "unconnected-(U1-USBD+-Pad17)") (class "Default")
      (node (ref "U1") (pin "17") (pinfunction "USBD+_17") (pintype "bidirectional"))
    )
    (net (code "208") (name "unconnected-(U1-USBD--Pad18)") (class "Default")
      (node (ref "U1") (pin "18") (pinfunction "USBD-_18") (pintype "bidirectional"))
    )
    (net (code "209") (name "unconnected-(U2-VBAT-Pad2)") (class "Default")
      (node (ref "U2") (pin "2") (pinfunction "VBAT_2") (pintype "bidirectional"))
    )
  )
)
